# Control_Device_sch.net
KiCad netlist of a schematic drawn in Altium Designer
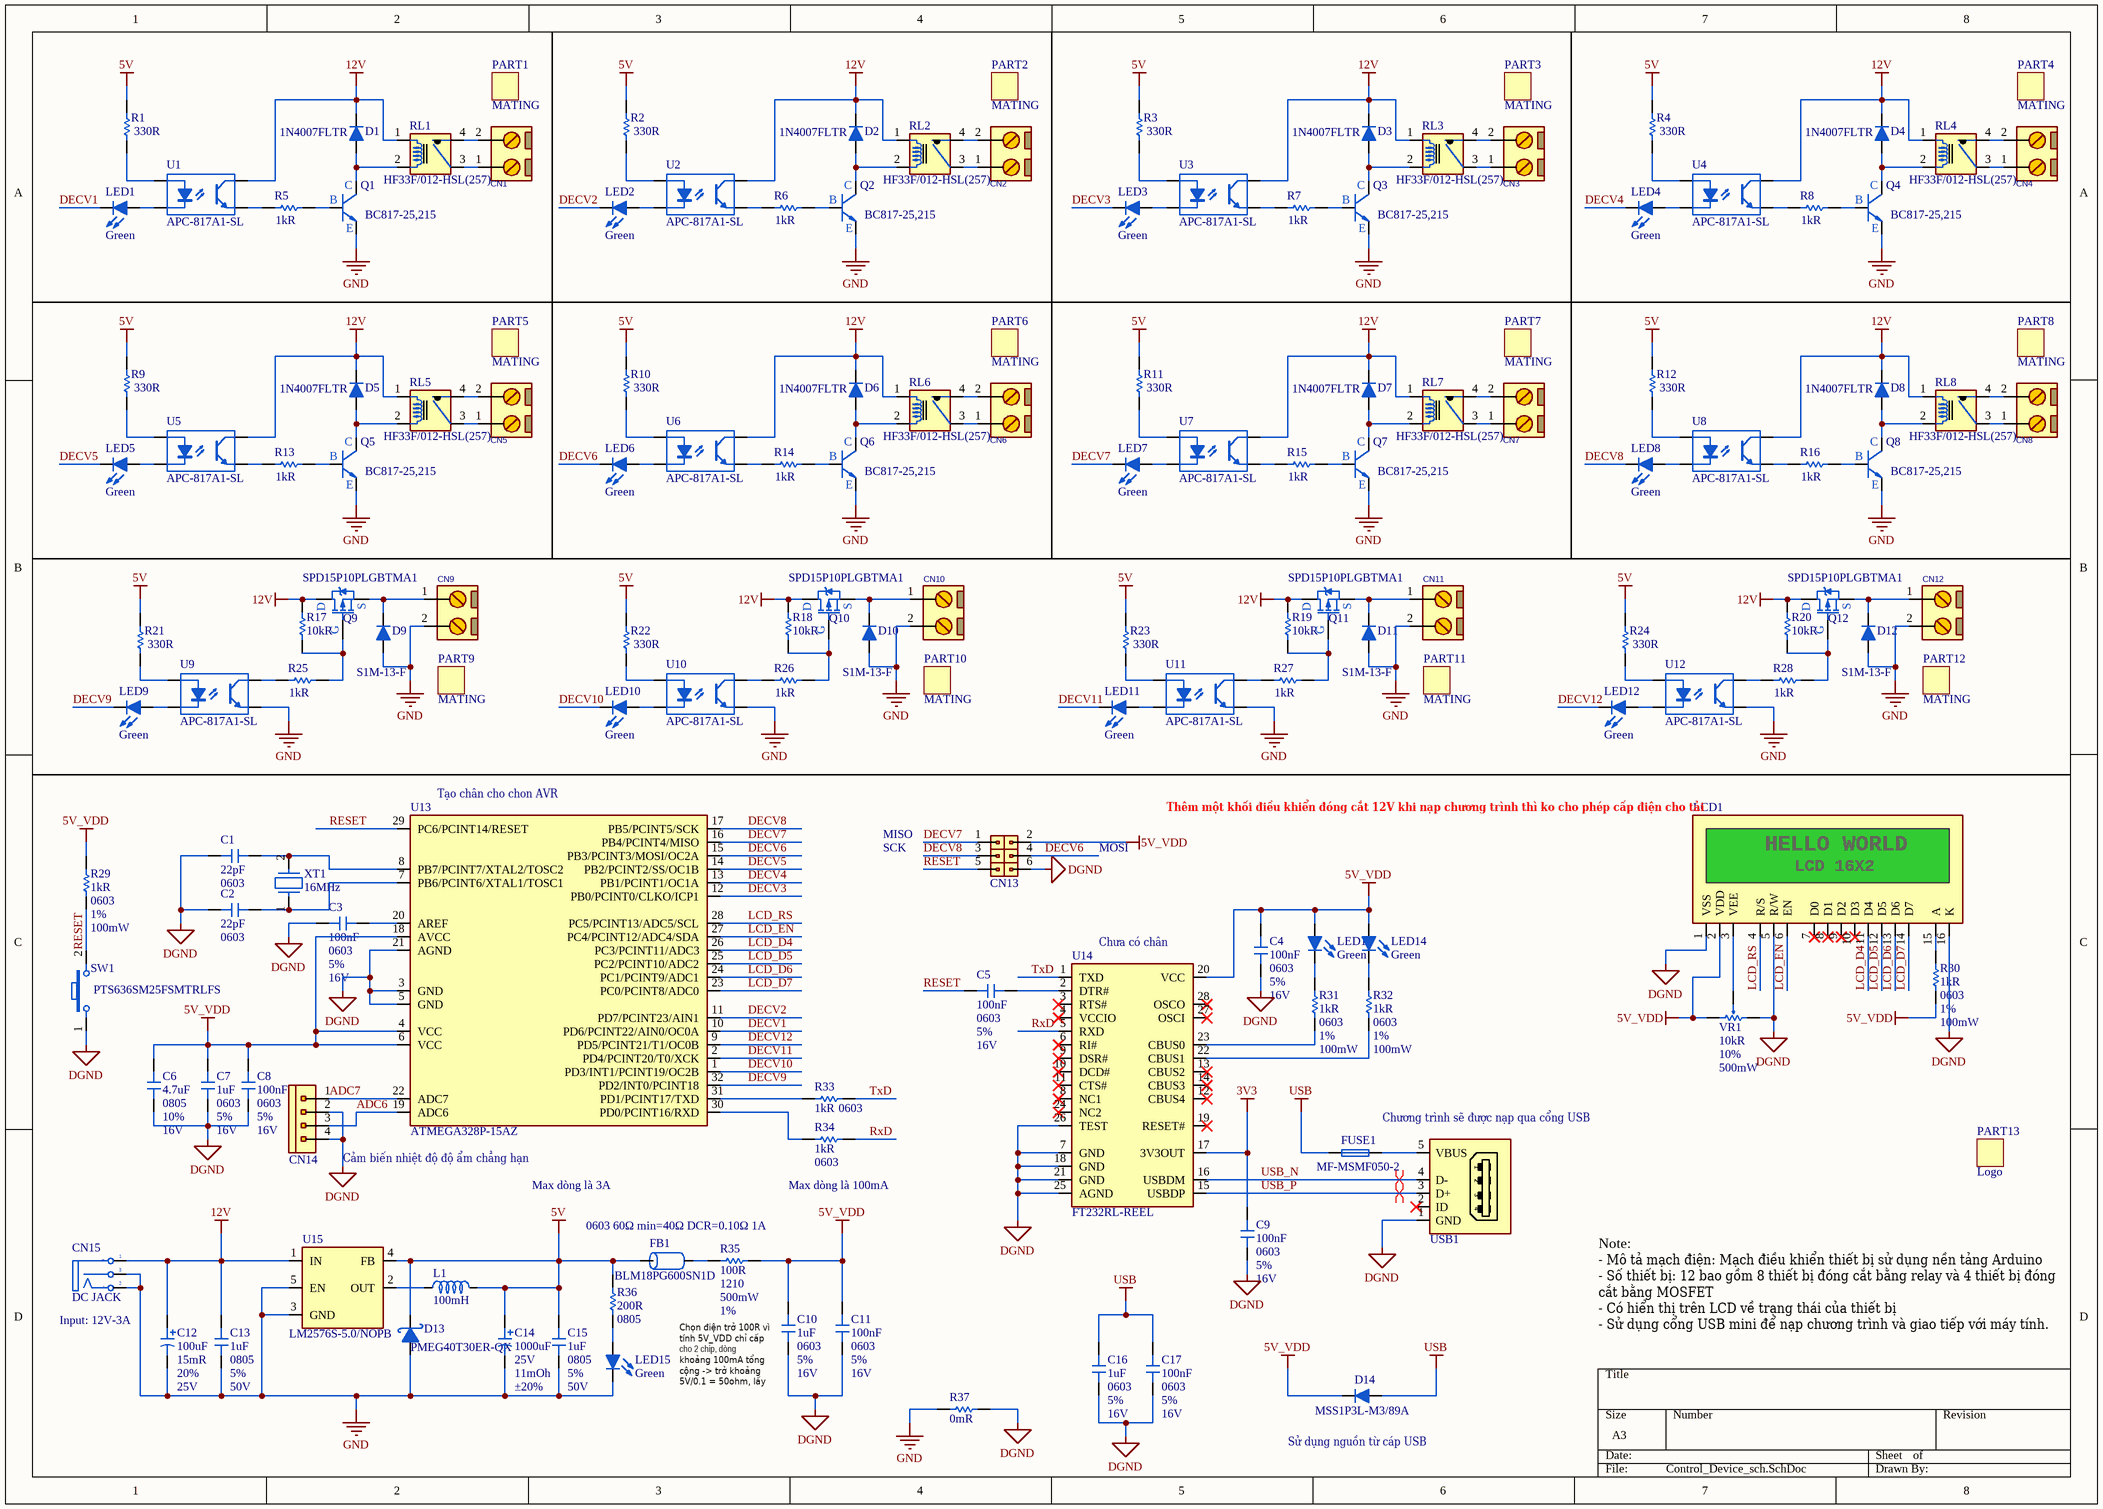
[diagram p0: Control_Device_sch.SchDoc]

(export (version "E")
  (design (tool "Eeschema 10.0.6"))
  (components
    (comp (ref "C1")
      (value "22pF")
      (footprint "C0603E")
      (description "Surface Mount Ceramic Multilayer Capacitor 22pF 5% C0G 50V 0603 Paper T/R")
      (fields
        (field (name "MANUFACTURER") "Yageo")
        (field (name "MANUFACTURER PART NUMBER") "CC0603JRNPO9BN220")
        (field (name "CASE/PACKAGE") "0603")
        (field (name "CREATOR") "hoangpt")
      )
      (libsource (lib "hoangpt") (part "CAP-CER"))
    )
    (comp (ref "C2")
      (value "22pF")
      (footprint "C0603E")
      (description "Surface Mount Ceramic Multilayer Capacitor 22pF 5% C0G 50V 0603 Paper T/R")
      (fields
        (field (name "MANUFACTURER") "Yageo")
        (field (name "MANUFACTURER PART NUMBER") "CC0603JRNPO9BN220")
        (field (name "CASE/PACKAGE") "0603")
        (field (name "CREATOR") "hoangpt")
      )
      (libsource (lib "hoangpt") (part "CAP-CER"))
    )
    (comp (ref "C3")
      (value "100nF")
      (footprint "C0603E")
      (description "Cap Ceramic 0.1uF 16V X7R 5% SMD 0603 125C T/R")
      (fields
        (field (name "MANUFACTURER") "Yageo")
        (field (name "MANUFACTURER PART NUMBER") "CC0603JRX7R7BB104")
        (field (name "CASE/PACKAGE") "0603")
        (field (name "TOLERANCE") "5%")
        (field (name "VOLTAGE RATING") "16V")
        (field (name "CREATOR") "hoangpt")
      )
      (libsource (lib "hoangpt") (part "CAP-CER"))
    )
    (comp (ref "C4")
      (value "100nF")
      (footprint "C0603E")
      (description "Cap Ceramic 0.1uF 16V X7R 5% SMD 0603 125C T/R")
      (fields
        (field (name "MANUFACTURER") "Yageo")
        (field (name "MANUFACTURER PART NUMBER") "CC0603JRX7R7BB104")
        (field (name "CASE/PACKAGE") "0603")
        (field (name "TOLERANCE") "5%")
        (field (name "VOLTAGE RATING") "16V")
        (field (name "CREATOR") "hoangpt")
      )
      (libsource (lib "hoangpt") (part "CAP-CER"))
    )
    (comp (ref "C5")
      (value "100nF")
      (footprint "C0603E")
      (description "Cap Ceramic 0.1uF 16V X7R 5% SMD 0603 125C T/R")
      (fields
        (field (name "MANUFACTURER") "Yageo")
        (field (name "MANUFACTURER PART NUMBER") "CC0603JRX7R7BB104")
        (field (name "CASE/PACKAGE") "0603")
        (field (name "TOLERANCE") "5%")
        (field (name "VOLTAGE RATING") "16V")
        (field (name "CREATOR") "hoangpt")
      )
      (libsource (lib "hoangpt") (part "CAP-CER"))
    )
    (comp (ref "C6")
      (value "4.7uF")
      (footprint "C0603E")
      (description "0805 4.7 uF 16 V ±10% Tolerance X5R Multilayer Ceramic Capacitor")
      (fields
        (field (name "MANUFACTURER") "Yageo")
        (field (name "MANUFACTURER PART NUMBER") "CC0805KKX5R7BB475")
        (field (name "CASE/PACKAGE") "0805")
        (field (name "TOLERANCE") "10%")
        (field (name "VOLTAGE RATING") "16V")
        (field (name "CREATOR") "hoangpt")
      )
      (libsource (lib "hoangpt") (part "CAP-CER"))
    )
    (comp (ref "C7")
      (value "1uF")
      (footprint "C0603E")
      (description "Cap Ceramic 1uF 16V X7R 5% SMD 0603 125°C Paper T/R")
      (fields
        (field (name "MANUFACTURER") "Yageo")
        (field (name "MANUFACTURER PART NUMBER") "CC0603JRX7R7BB105")
        (field (name "CASE/PACKAGE") "0603")
        (field (name "TOLERANCE") "5%")
        (field (name "VOLTAGE RATING") "16V")
        (field (name "CREATOR") "hoangpt")
      )
      (libsource (lib "hoangpt") (part "CAP-CER"))
    )
    (comp (ref "C8")
      (value "100nF")
      (footprint "C0603E")
      (description "Cap Ceramic 0.1uF 16V X7R 5% SMD 0603 125C T/R")
      (fields
        (field (name "MANUFACTURER") "Yageo")
        (field (name "MANUFACTURER PART NUMBER") "CC0603JRX7R7BB104")
        (field (name "CASE/PACKAGE") "0603")
        (field (name "TOLERANCE") "5%")
        (field (name "VOLTAGE RATING") "16V")
        (field (name "CREATOR") "hoangpt")
      )
      (libsource (lib "hoangpt") (part "CAP-CER"))
    )
    (comp (ref "C9")
      (value "100nF")
      (footprint "C0603E")
      (description "Cap Ceramic 0.1uF 16V X7R 5% SMD 0603 125C T/R")
      (fields
        (field (name "MANUFACTURER") "Yageo")
        (field (name "MANUFACTURER PART NUMBER") "CC0603JRX7R7BB104")
        (field (name "CASE/PACKAGE") "0603")
        (field (name "TOLERANCE") "5%")
        (field (name "VOLTAGE RATING") "16V")
        (field (name "CREATOR") "hoangpt")
      )
      (libsource (lib "hoangpt") (part "CAP-CER"))
    )
    (comp (ref "C10")
      (value "1uF")
      (footprint "C0603E")
      (description "Cap Ceramic 1uF 16V X7R 5% SMD 0603 125°C Paper T/R")
      (fields
        (field (name "MANUFACTURER") "Yageo")
        (field (name "MANUFACTURER PART NUMBER") "CC0603JRX7R7BB105")
        (field (name "CASE/PACKAGE") "0603")
        (field (name "TOLERANCE") "5%")
        (field (name "VOLTAGE RATING") "16V")
        (field (name "CREATOR") "hoangpt")
      )
      (libsource (lib "hoangpt") (part "CAP-CER"))
    )
    (comp (ref "C11")
      (value "100nF")
      (footprint "C0603E")
      (description "Cap Ceramic 0.1uF 16V X7R 5% SMD 0603 125C T/R")
      (fields
        (field (name "MANUFACTURER") "Yageo")
        (field (name "MANUFACTURER PART NUMBER") "CC0603JRX7R7BB104")
        (field (name "CASE/PACKAGE") "0603")
        (field (name "TOLERANCE") "5%")
        (field (name "VOLTAGE RATING") "16V")
        (field (name "CREATOR") "hoangpt")
      )
      (libsource (lib "hoangpt") (part "CAP-CER"))
    )
    (comp (ref "C12")
      (value "100uF")
      (footprint "CAP_ELEC_500_12X25_THD")
      (description "Cap Aluminum Polymer 100uF 25VDC 20% (10 X 12.5mm) Radial 5mm 0.015 Ohm 4500mA 2000h 105C T/R")
      (fields
        (field (name "MANUFACTURER") "Nichicon")
        (field (name "MANUFACTURER PART NUMBER") "RNS1E101MDN1PH")
        (field (name "ESR (EQUIVALENT SERIES RESISTANCE)") "15mR")
        (field (name "TOLERANCE") "20%")
        (field (name "VOLTAGE RATING") "25V")
        (field (name "CREATOR") "hoangpt")
      )
      (libsource (lib "hoangpt") (part "CAP-ELEC"))
    )
    (comp (ref "C13")
      (value "1uF")
      (footprint "C0805E")
      (description "0805 1 uF 50 V ±5 % Tolerance X7R Surface Mount Multilayer Ceramic Capacitor")
      (fields
        (field (name "MANUFACTURER") "Yageo")
        (field (name "MANUFACTURER PART NUMBER") "CC0805JKX7R9BB105")
        (field (name "CASE/PACKAGE") "0805")
        (field (name "TOLERANCE") "5%")
        (field (name "VOLTAGE RATING") "50V")
        (field (name "CREATOR") "hoangpt")
      )
      (libsource (lib "hoangpt") (part "CAP-CER"))
    )
    (comp (ref "C14")
      (value "1000uF")
      (footprint "CAP_ELEC_500_10X16_THD")
      (description "Cap, 1000Uf, 25V, Alu Elec, Hybrid, Rad Rohs Compliant: Yes")
      (fields
        (field (name "MANUFACTURER") "Panasonic")
        (field (name "MANUFACTURER PART NUMBER") "EEHAZSE102UB")
        (field (name "VOLTAGE") "25V")
        (field (name "ERS") "11mOh")
        (field (name "TOLERANCE") "±20%")
        (field (name "CREATOR") "hoangpt")
      )
      (libsource (lib "hoangpt") (part "CAP-ELEC"))
    )
    (comp (ref "C15")
      (value "1uF")
      (footprint "C0805E")
      (description "0805 1 uF 50 V ±5 % Tolerance X7R Surface Mount Multilayer Ceramic Capacitor")
      (fields
        (field (name "MANUFACTURER") "Yageo")
        (field (name "MANUFACTURER PART NUMBER") "CC0805JKX7R9BB105")
        (field (name "CASE/PACKAGE") "0805")
        (field (name "TOLERANCE") "5%")
        (field (name "VOLTAGE RATING") "50V")
        (field (name "CREATOR") "hoangpt")
      )
      (libsource (lib "hoangpt") (part "CAP-CER"))
    )
    (comp (ref "C16")
      (value "1uF")
      (footprint "C0603E")
      (description "Cap Ceramic 1uF 16V X7R 5% SMD 0603 125°C Paper T/R")
      (fields
        (field (name "MANUFACTURER") "Yageo")
        (field (name "MANUFACTURER PART NUMBER") "CC0603JRX7R7BB105")
        (field (name "CASE/PACKAGE") "0603")
        (field (name "TOLERANCE") "5%")
        (field (name "VOLTAGE RATING") "16V")
        (field (name "CREATOR") "hoangpt")
      )
      (libsource (lib "hoangpt") (part "CAP-CER"))
    )
    (comp (ref "C17")
      (value "100nF")
      (footprint "C0603E")
      (description "Cap Ceramic 0.1uF 16V X7R 5% SMD 0603 125C T/R")
      (fields
        (field (name "MANUFACTURER") "Yageo")
        (field (name "MANUFACTURER PART NUMBER") "CC0603JRX7R7BB104")
        (field (name "CASE/PACKAGE") "0603")
        (field (name "TOLERANCE") "5%")
        (field (name "VOLTAGE RATING") "16V")
        (field (name "CREATOR") "hoangpt")
      )
      (libsource (lib "hoangpt") (part "CAP-CER"))
    )
    (comp (ref "CN1")
      (value "~")
      (footprint "CON_PWR_508_H_2P")
      (description "Conn Shrouded Header (2 Sides) M 2 POS 5mm Solder RA Side Entry Thru-Hole Box")
      (fields
        (field (name "MANUFACTURER") "TE Connectivity")
        (field (name "MANUFACTURER PART NUMBER") "282812-2")
        (field (name "CREATOR") "hoangpt")
      )
      (libsource (lib "hoangpt") (part "CONN_PWR_2P"))
    )
    (comp (ref "CN2")
      (value "~")
      (footprint "CON_PWR_508_H_2P")
      (description "Conn Shrouded Header (2 Sides) M 2 POS 5mm Solder RA Side Entry Thru-Hole Box")
      (fields
        (field (name "MANUFACTURER") "TE Connectivity")
        (field (name "MANUFACTURER PART NUMBER") "282812-2")
        (field (name "CREATOR") "hoangpt")
      )
      (libsource (lib "hoangpt") (part "CONN_PWR_2P"))
    )
    (comp (ref "CN3")
      (value "~")
      (footprint "CON_PWR_508_H_2P")
      (description "Conn Shrouded Header (2 Sides) M 2 POS 5mm Solder RA Side Entry Thru-Hole Box")
      (fields
        (field (name "MANUFACTURER") "TE Connectivity")
        (field (name "MANUFACTURER PART NUMBER") "282812-2")
        (field (name "CREATOR") "hoangpt")
      )
      (libsource (lib "hoangpt") (part "CONN_PWR_2P"))
    )
    (comp (ref "CN4")
      (value "~")
      (footprint "CON_PWR_508_H_2P")
      (description "Conn Shrouded Header (2 Sides) M 2 POS 5mm Solder RA Side Entry Thru-Hole Box")
      (fields
        (field (name "MANUFACTURER") "TE Connectivity")
        (field (name "MANUFACTURER PART NUMBER") "282812-2")
        (field (name "CREATOR") "hoangpt")
      )
      (libsource (lib "hoangpt") (part "CONN_PWR_2P"))
    )
    (comp (ref "CN5")
      (value "~")
      (footprint "CON_PWR_508_H_2P")
      (description "Conn Shrouded Header (2 Sides) M 2 POS 5mm Solder RA Side Entry Thru-Hole Box")
      (fields
        (field (name "MANUFACTURER") "TE Connectivity")
        (field (name "MANUFACTURER PART NUMBER") "282812-2")
        (field (name "CREATOR") "hoangpt")
      )
      (libsource (lib "hoangpt") (part "CONN_PWR_2P"))
    )
    (comp (ref "CN6")
      (value "~")
      (footprint "CON_PWR_508_H_2P")
      (description "Conn Shrouded Header (2 Sides) M 2 POS 5mm Solder RA Side Entry Thru-Hole Box")
      (fields
        (field (name "MANUFACTURER") "TE Connectivity")
        (field (name "MANUFACTURER PART NUMBER") "282812-2")
        (field (name "CREATOR") "hoangpt")
      )
      (libsource (lib "hoangpt") (part "CONN_PWR_2P"))
    )
    (comp (ref "CN7")
      (value "~")
      (footprint "CON_PWR_508_H_2P")
      (description "Conn Shrouded Header (2 Sides) M 2 POS 5mm Solder RA Side Entry Thru-Hole Box")
      (fields
        (field (name "MANUFACTURER") "TE Connectivity")
        (field (name "MANUFACTURER PART NUMBER") "282812-2")
        (field (name "CREATOR") "hoangpt")
      )
      (libsource (lib "hoangpt") (part "CONN_PWR_2P"))
    )
    (comp (ref "CN8")
      (value "~")
      (footprint "CON_PWR_508_H_2P")
      (description "Conn Shrouded Header (2 Sides) M 2 POS 5mm Solder RA Side Entry Thru-Hole Box")
      (fields
        (field (name "MANUFACTURER") "TE Connectivity")
        (field (name "MANUFACTURER PART NUMBER") "282812-2")
        (field (name "CREATOR") "hoangpt")
      )
      (libsource (lib "hoangpt") (part "CONN_PWR_2P"))
    )
    (comp (ref "CN9")
      (value "~")
      (footprint "CON_PWR_508_H_2P")
      (description "Conn Shrouded Header (2 Sides) M 2 POS 5mm Solder RA Side Entry Thru-Hole Box")
      (fields
        (field (name "MANUFACTURER") "TE Connectivity")
        (field (name "MANUFACTURER PART NUMBER") "282812-2")
        (field (name "CREATOR") "hoangpt")
      )
      (libsource (lib "") (part "CONN_PWR_2P_1"))
    )
    (comp (ref "CN10")
      (value "~")
      (footprint "CON_PWR_508_H_2P")
      (description "Conn Shrouded Header (2 Sides) M 2 POS 5mm Solder RA Side Entry Thru-Hole Box")
      (fields
        (field (name "MANUFACTURER") "TE Connectivity")
        (field (name "MANUFACTURER PART NUMBER") "282812-2")
        (field (name "CREATOR") "hoangpt")
      )
      (libsource (lib "") (part "CONN_PWR_2P_1"))
    )
    (comp (ref "CN11")
      (value "~")
      (footprint "CON_PWR_508_H_2P")
      (description "Conn Shrouded Header (2 Sides) M 2 POS 5mm Solder RA Side Entry Thru-Hole Box")
      (fields
        (field (name "MANUFACTURER") "TE Connectivity")
        (field (name "MANUFACTURER PART NUMBER") "282812-2")
        (field (name "CREATOR") "hoangpt")
      )
      (libsource (lib "") (part "CONN_PWR_2P_1"))
    )
    (comp (ref "CN12")
      (value "~")
      (footprint "CON_PWR_508_H_2P")
      (description "Conn Shrouded Header (2 Sides) M 2 POS 5mm Solder RA Side Entry Thru-Hole Box")
      (fields
        (field (name "MANUFACTURER") "TE Connectivity")
        (field (name "MANUFACTURER PART NUMBER") "282812-2")
        (field (name "CREATOR") "hoangpt")
      )
      (libsource (lib "") (part "CONN_PWR_2P_1"))
    )
    (comp (ref "CN13")
      (value "PEC03DAAN")
      (footprint "CON_JPR_254_M_2X3")
      (description "CONN HEADER VERT 6POS 2.54MM")
      (fields (field (name "MANUFACTURER") "Sullins") (field (name "CREATOR") "hoangpt"))
      (libsource (lib "hoangpt") (part "CONN_FM_2X3P"))
    )
    (comp (ref "CN14")
      (value "~")
      (footprint "CON_JPR_254_M_1X4")
      (description "PEC Series Single Row 4 Position 2.54 mm Straight Breakaway Header")
      (fields
        (field (name "MANUFACTURER") "Sullins")
        (field (name "MANUFACTURER PART NUMBER") "PEC04SAAN")
        (field (name "CREATOR") "hoangpt")
      )
      (libsource (lib "hoangpt") (part "CONN_JP_4P"))
    )
    (comp (ref "CN15")
      (value "DC JACK")
      (footprint "JAC_DC_2MM_THD")
      (description "2.0 x 6.5 mm, 2.5 A, Horizontal, Through Hole, Dc Power Jack Connector")
      (fields (field (name "MANUFACTURER") "CUI") (field (name "MANUFACTURER PART NUMBER") "PJ-002A"))
      (libsource (lib "hoangpt") (part "DC_JACK"))
    )
    (comp (ref "D1")
      (value "1N4007FLTR")
      (footprint "D1206_SOD123_DO213AA")
      (description "Standard Rectifier 1000V SOD-123")
      (fields (field (name "MANUFACTURER") "SMC") (field (name "CREATOR") "hoangpt"))
      (libsource (lib "hoangpt") (part "DIODE"))
    )
    (comp (ref "D2")
      (value "1N4007FLTR")
      (footprint "D1206_SOD123_DO213AA")
      (description "Standard Rectifier 1000V SOD-123")
      (fields (field (name "MANUFACTURER") "SMC") (field (name "CREATOR") "hoangpt"))
      (libsource (lib "hoangpt") (part "DIODE"))
    )
    (comp (ref "D3")
      (value "1N4007FLTR")
      (footprint "D1206_SOD123_DO213AA")
      (description "Standard Rectifier 1000V SOD-123")
      (fields (field (name "MANUFACTURER") "SMC") (field (name "CREATOR") "hoangpt"))
      (libsource (lib "hoangpt") (part "DIODE"))
    )
    (comp (ref "D4")
      (value "1N4007FLTR")
      (footprint "D1206_SOD123_DO213AA")
      (description "Standard Rectifier 1000V SOD-123")
      (fields (field (name "MANUFACTURER") "SMC") (field (name "CREATOR") "hoangpt"))
      (libsource (lib "hoangpt") (part "DIODE"))
    )
    (comp (ref "D5")
      (value "1N4007FLTR")
      (footprint "D1206_SOD123_DO213AA")
      (description "Standard Rectifier 1000V SOD-123")
      (fields (field (name "MANUFACTURER") "SMC") (field (name "CREATOR") "hoangpt"))
      (libsource (lib "hoangpt") (part "DIODE"))
    )
    (comp (ref "D6")
      (value "1N4007FLTR")
      (footprint "D1206_SOD123_DO213AA")
      (description "Standard Rectifier 1000V SOD-123")
      (fields (field (name "MANUFACTURER") "SMC") (field (name "CREATOR") "hoangpt"))
      (libsource (lib "hoangpt") (part "DIODE"))
    )
    (comp (ref "D7")
      (value "1N4007FLTR")
      (footprint "D1206_SOD123_DO213AA")
      (description "Standard Rectifier 1000V SOD-123")
      (fields (field (name "MANUFACTURER") "SMC") (field (name "CREATOR") "hoangpt"))
      (libsource (lib "hoangpt") (part "DIODE"))
    )
    (comp (ref "D8")
      (value "1N4007FLTR")
      (footprint "D1206_SOD123_DO213AA")
      (description "Standard Rectifier 1000V SOD-123")
      (fields (field (name "MANUFACTURER") "SMC") (field (name "CREATOR") "hoangpt"))
      (libsource (lib "hoangpt") (part "DIODE"))
    )
    (comp (ref "D9")
      (value "S1M-13-F")
      (footprint "DIODE_SMA")
      (description "VR=1000V IF=1A 10pF Trr=3us")
      (fields (field (name "MANUFACTURER") "Diodes") (field (name "CREATOR") "hoangpt"))
      (libsource (lib "hoangpt") (part "DIODE"))
    )
    (comp (ref "D10")
      (value "S1M-13-F")
      (footprint "DIODE_SMA")
      (description "VR=1000V IF=1A 10pF Trr=3us")
      (fields (field (name "MANUFACTURER") "Diodes") (field (name "CREATOR") "hoangpt"))
      (libsource (lib "hoangpt") (part "DIODE"))
    )
    (comp (ref "D11")
      (value "S1M-13-F")
      (footprint "DIODE_SMA")
      (description "VR=1000V IF=1A 10pF Trr=3us")
      (fields (field (name "MANUFACTURER") "Diodes") (field (name "CREATOR") "hoangpt"))
      (libsource (lib "hoangpt") (part "DIODE"))
    )
    (comp (ref "D12")
      (value "S1M-13-F")
      (footprint "DIODE_SMA")
      (description "VR=1000V IF=1A 10pF Trr=3us")
      (fields (field (name "MANUFACTURER") "Diodes") (field (name "CREATOR") "hoangpt"))
      (libsource (lib "hoangpt") (part "DIODE"))
    )
    (comp (ref "D13")
      (value "PMEG40T30ER-QX")
      (footprint "DIODE_SOD123W")
      (description "PMEG40T30ER-Q - 40 V, 3 A low Trench MEGA Schottky barrier rectifier")
      (fields (field (name "MANUFACTURER") "Nexperia") (field (name "CREATOR") "hoangpt"))
      (libsource (lib "hoangpt") (part "DIODE_SCHOTTKY"))
    )
    (comp (ref "D14")
      (value "MSS1P3L-M3/89A")
      (footprint "DIODE_S457")
      (description "VR=30V IF=1A 65pF")
      (fields (field (name "MANUFACTURER") "Vishay Semiconductors") (field (name "CREATOR") "hoangpt"))
      (libsource (lib "hoangpt") (part "DIODE"))
    )
    (comp (ref "FB1")
      (value "BLM18PG600SN1D")
      (footprint "IND_L0603E_1608")
      (description "0603 60Ω min=40Ω DCR=0.10Ω 1A")
      (fields
        (field (name "MANUFACTURER") "Murata")
        (field (name "TOLERANCE") "25%")
        (field (name "CREATOR") "hoangpt")
      )
      (libsource (lib "hoangpt") (part "FERRITE BEAD"))
    )
    (comp (ref "FUSE1")
      (value "MF-MSMF050-2")
      (footprint "RFUSE")
      (description "15VDC 500mA")
      (fields (field (name "MANUFACTURER") "Bourns") (field (name "CREATOR") "hoangpt"))
      (libsource (lib "hoangpt") (part "FUSE_RESETTABLE"))
    )
    (comp (ref "L1")
      (value "100mH")
      (footprint "L_12X12")
      (description "INDUCTOR_AIR")
      (fields
        (field (name "MANUFACTURER") "Bourns")
        (field (name "MANUFACTURER PART NUMBER") "SRN3015C-101M")
        (field (name "CREATOR") "hoangpt")
      )
      (libsource (lib "hoangpt") (part "INDUCTOR_AIR"))
    )
    (comp (ref "LCD1")
      (value "~")
      (footprint "LCD_16x2")
      (description "16 x 2 Transflective White LED Backlight LCD Character Module with Heater")
      (fields
        (field (name "MANUFACTURER") "Lumex")
        (field (name "MANUFACTURER PART NUMBER") "LCR-U01602DSF/AWH")
        (field (name "CREATOR") "hoangpt")
      )
      (libsource (lib "hoangpt") (part "LCD_16X2"))
    )
    (comp (ref "LED1")
      (value "Green")
      (footprint "LED0603")
      (description "LED, Green, SMD 0805, 7.0 mcd, Green Diffused Lens")
      (fields
        (field (name "MANUFACTURER") "VCC CHML")
        (field (name "MANUFACTURER PART NUMBER") "CMD17-21VGD/TR8")
        (field (name "CREATOR") "hoangpt")
      )
      (libsource (lib "hoangpt") (part "LED"))
    )
    (comp (ref "LED2")
      (value "Green")
      (footprint "LED0603")
      (description "LED, Green, SMD 0805, 7.0 mcd, Green Diffused Lens")
      (fields
        (field (name "MANUFACTURER") "VCC CHML")
        (field (name "MANUFACTURER PART NUMBER") "CMD17-21VGD/TR8")
        (field (name "CREATOR") "hoangpt")
      )
      (libsource (lib "hoangpt") (part "LED"))
    )
    (comp (ref "LED3")
      (value "Green")
      (footprint "LED0603")
      (description "LED, Green, SMD 0805, 7.0 mcd, Green Diffused Lens")
      (fields
        (field (name "MANUFACTURER") "VCC CHML")
        (field (name "MANUFACTURER PART NUMBER") "CMD17-21VGD/TR8")
        (field (name "CREATOR") "hoangpt")
      )
      (libsource (lib "hoangpt") (part "LED"))
    )
    (comp (ref "LED4")
      (value "Green")
      (footprint "LED0603")
      (description "LED, Green, SMD 0805, 7.0 mcd, Green Diffused Lens")
      (fields
        (field (name "MANUFACTURER") "VCC CHML")
        (field (name "MANUFACTURER PART NUMBER") "CMD17-21VGD/TR8")
        (field (name "CREATOR") "hoangpt")
      )
      (libsource (lib "hoangpt") (part "LED"))
    )
    (comp (ref "LED5")
      (value "Green")
      (footprint "LED0603")
      (description "LED, Green, SMD 0805, 7.0 mcd, Green Diffused Lens")
      (fields
        (field (name "MANUFACTURER") "VCC CHML")
        (field (name "MANUFACTURER PART NUMBER") "CMD17-21VGD/TR8")
        (field (name "CREATOR") "hoangpt")
      )
      (libsource (lib "hoangpt") (part "LED"))
    )
    (comp (ref "LED6")
      (value "Green")
      (footprint "LED0603")
      (description "LED, Green, SMD 0805, 7.0 mcd, Green Diffused Lens")
      (fields
        (field (name "MANUFACTURER") "VCC CHML")
        (field (name "MANUFACTURER PART NUMBER") "CMD17-21VGD/TR8")
        (field (name "CREATOR") "hoangpt")
      )
      (libsource (lib "hoangpt") (part "LED"))
    )
    (comp (ref "LED7")
      (value "Green")
      (footprint "LED0603")
      (description "LED, Green, SMD 0805, 7.0 mcd, Green Diffused Lens")
      (fields
        (field (name "MANUFACTURER") "VCC CHML")
        (field (name "MANUFACTURER PART NUMBER") "CMD17-21VGD/TR8")
        (field (name "CREATOR") "hoangpt")
      )
      (libsource (lib "hoangpt") (part "LED"))
    )
    (comp (ref "LED8")
      (value "Green")
      (footprint "LED0603")
      (description "LED, Green, SMD 0805, 7.0 mcd, Green Diffused Lens")
      (fields
        (field (name "MANUFACTURER") "VCC CHML")
        (field (name "MANUFACTURER PART NUMBER") "CMD17-21VGD/TR8")
        (field (name "CREATOR") "hoangpt")
      )
      (libsource (lib "hoangpt") (part "LED"))
    )
    (comp (ref "LED9")
      (value "Green")
      (footprint "LED0603")
      (description "LED, Green, SMD 0805, 7.0 mcd, Green Diffused Lens")
      (fields
        (field (name "MANUFACTURER") "VCC CHML")
        (field (name "MANUFACTURER PART NUMBER") "CMD17-21VGD/TR8")
        (field (name "CREATOR") "hoangpt")
      )
      (libsource (lib "hoangpt") (part "LED"))
    )
    (comp (ref "LED10")
      (value "Green")
      (footprint "LED0603")
      (description "LED, Green, SMD 0805, 7.0 mcd, Green Diffused Lens")
      (fields
        (field (name "MANUFACTURER") "VCC CHML")
        (field (name "MANUFACTURER PART NUMBER") "CMD17-21VGD/TR8")
        (field (name "CREATOR") "hoangpt")
      )
      (libsource (lib "hoangpt") (part "LED"))
    )
    (comp (ref "LED11")
      (value "Green")
      (footprint "LED0603")
      (description "LED, Green, SMD 0805, 7.0 mcd, Green Diffused Lens")
      (fields
        (field (name "MANUFACTURER") "VCC CHML")
        (field (name "MANUFACTURER PART NUMBER") "CMD17-21VGD/TR8")
        (field (name "CREATOR") "hoangpt")
      )
      (libsource (lib "hoangpt") (part "LED"))
    )
    (comp (ref "LED12")
      (value "Green")
      (footprint "LED0603")
      (description "LED, Green, SMD 0805, 7.0 mcd, Green Diffused Lens")
      (fields
        (field (name "MANUFACTURER") "VCC CHML")
        (field (name "MANUFACTURER PART NUMBER") "CMD17-21VGD/TR8")
        (field (name "CREATOR") "hoangpt")
      )
      (libsource (lib "hoangpt") (part "LED"))
    )
    (comp (ref "LED13")
      (value "Green")
      (footprint "LED0603")
      (description "LED, Green, SMD 0805, 7.0 mcd, Green Diffused Lens")
      (fields
        (field (name "MANUFACTURER") "VCC CHML")
        (field (name "MANUFACTURER PART NUMBER") "CMD17-21VGD/TR8")
        (field (name "CREATOR") "hoangpt")
      )
      (libsource (lib "hoangpt") (part "LED"))
    )
    (comp (ref "LED14")
      (value "Green")
      (footprint "LED0603")
      (description "LED, Green, SMD 0805, 7.0 mcd, Green Diffused Lens")
      (fields
        (field (name "MANUFACTURER") "VCC CHML")
        (field (name "MANUFACTURER PART NUMBER") "CMD17-21VGD/TR8")
        (field (name "CREATOR") "hoangpt")
      )
      (libsource (lib "hoangpt") (part "LED"))
    )
    (comp (ref "LED15")
      (value "Green")
      (footprint "LED0603")
      (description "LED, Green, SMD 0805, 7.0 mcd, Green Diffused Lens")
      (fields
        (field (name "MANUFACTURER") "VCC CHML")
        (field (name "MANUFACTURER PART NUMBER") "CMD17-21VGD/TR8")
        (field (name "CREATOR") "hoangpt")
      )
      (libsource (lib "hoangpt") (part "LED"))
    )
    (comp (ref "PART1")
      (value "MATING")
      (description "Conn Terminal Block F 2 POS 5mm Screw RA Cable Mount 15A/Contact")
      (fields
        (field (name "MANUFACTURER") "TE Connectivity")
        (field (name "MANUFACTURER PART NUMBER") "796640-2")
      )
      (libsource (lib "hoangpt") (part "PART_NO-BOM"))
    )
    (comp (ref "PART2")
      (value "MATING")
      (description "Conn Terminal Block F 2 POS 5mm Screw RA Cable Mount 15A/Contact")
      (fields
        (field (name "MANUFACTURER") "TE Connectivity")
        (field (name "MANUFACTURER PART NUMBER") "796640-2")
      )
      (libsource (lib "hoangpt") (part "PART_NO-BOM"))
    )
    (comp (ref "PART3")
      (value "MATING")
      (description "Conn Terminal Block F 2 POS 5mm Screw RA Cable Mount 15A/Contact")
      (fields
        (field (name "MANUFACTURER") "TE Connectivity")
        (field (name "MANUFACTURER PART NUMBER") "796640-2")
      )
      (libsource (lib "hoangpt") (part "PART_NO-BOM"))
    )
    (comp (ref "PART4")
      (value "MATING")
      (description "Conn Terminal Block F 2 POS 5mm Screw RA Cable Mount 15A/Contact")
      (fields
        (field (name "MANUFACTURER") "TE Connectivity")
        (field (name "MANUFACTURER PART NUMBER") "796640-2")
      )
      (libsource (lib "hoangpt") (part "PART_NO-BOM"))
    )
    (comp (ref "PART5")
      (value "MATING")
      (description "Conn Terminal Block F 2 POS 5mm Screw RA Cable Mount 15A/Contact")
      (fields
        (field (name "MANUFACTURER") "TE Connectivity")
        (field (name "MANUFACTURER PART NUMBER") "796640-2")
      )
      (libsource (lib "hoangpt") (part "PART_NO-BOM"))
    )
    (comp (ref "PART6")
      (value "MATING")
      (description "Conn Terminal Block F 2 POS 5mm Screw RA Cable Mount 15A/Contact")
      (fields
        (field (name "MANUFACTURER") "TE Connectivity")
        (field (name "MANUFACTURER PART NUMBER") "796640-2")
      )
      (libsource (lib "hoangpt") (part "PART_NO-BOM"))
    )
    (comp (ref "PART7")
      (value "MATING")
      (description "Conn Terminal Block F 2 POS 5mm Screw RA Cable Mount 15A/Contact")
      (fields
        (field (name "MANUFACTURER") "TE Connectivity")
        (field (name "MANUFACTURER PART NUMBER") "796640-2")
      )
      (libsource (lib "hoangpt") (part "PART_NO-BOM"))
    )
    (comp (ref "PART8")
      (value "MATING")
      (description "Conn Terminal Block F 2 POS 5mm Screw RA Cable Mount 15A/Contact")
      (fields
        (field (name "MANUFACTURER") "TE Connectivity")
        (field (name "MANUFACTURER PART NUMBER") "796640-2")
      )
      (libsource (lib "hoangpt") (part "PART_NO-BOM"))
    )
    (comp (ref "PART9")
      (value "MATING")
      (description "Conn Terminal Block F 2 POS 5mm Screw RA Cable Mount 15A/Contact")
      (fields
        (field (name "MANUFACTURER") "TE Connectivity")
        (field (name "MANUFACTURER PART NUMBER") "796640-2")
      )
      (libsource (lib "hoangpt") (part "PART_NO-BOM"))
    )
    (comp (ref "PART10")
      (value "MATING")
      (description "Conn Terminal Block F 2 POS 5mm Screw RA Cable Mount 15A/Contact")
      (fields
        (field (name "MANUFACTURER") "TE Connectivity")
        (field (name "MANUFACTURER PART NUMBER") "796640-2")
      )
      (libsource (lib "hoangpt") (part "PART_NO-BOM"))
    )
    (comp (ref "PART11")
      (value "MATING")
      (description "Conn Terminal Block F 2 POS 5mm Screw RA Cable Mount 15A/Contact")
      (fields
        (field (name "MANUFACTURER") "TE Connectivity")
        (field (name "MANUFACTURER PART NUMBER") "796640-2")
      )
      (libsource (lib "hoangpt") (part "PART_NO-BOM"))
    )
    (comp (ref "PART12")
      (value "MATING")
      (description "Conn Terminal Block F 2 POS 5mm Screw RA Cable Mount 15A/Contact")
      (fields
        (field (name "MANUFACTURER") "TE Connectivity")
        (field (name "MANUFACTURER PART NUMBER") "796640-2")
      )
      (libsource (lib "hoangpt") (part "PART_NO-BOM"))
    )
    (comp (ref "PART13")
      (value "Logo")
      (footprint "MyLogo_5mm - Invert")
      (description "Conn Terminal Block F 2 POS 5mm Screw RA Cable Mount 15A/Contact")
      (libsource (lib "hoangpt") (part "PART_NO-BOM"))
    )
    (comp (ref "Q1")
      (value "BC817-25,215")
      (footprint "SOT23_3")
      (description "NPN Ic=500mA Vceo=45V hfe=160~400 P=250mW")
      (fields (field (name "MANUFACTURER") "Nexperia") (field (name "CREATOR") "hoangpt"))
      (libsource (lib "hoangpt") (part "NPN"))
    )
    (comp (ref "Q2")
      (value "BC817-25,215")
      (footprint "SOT23_3")
      (description "NPN Ic=500mA Vceo=45V hfe=160~400 P=250mW")
      (fields (field (name "MANUFACTURER") "Nexperia") (field (name "CREATOR") "hoangpt"))
      (libsource (lib "hoangpt") (part "NPN"))
    )
    (comp (ref "Q3")
      (value "BC817-25,215")
      (footprint "SOT23_3")
      (description "NPN Ic=500mA Vceo=45V hfe=160~400 P=250mW")
      (fields (field (name "MANUFACTURER") "Nexperia") (field (name "CREATOR") "hoangpt"))
      (libsource (lib "hoangpt") (part "NPN"))
    )
    (comp (ref "Q4")
      (value "BC817-25,215")
      (footprint "SOT23_3")
      (description "NPN Ic=500mA Vceo=45V hfe=160~400 P=250mW")
      (fields (field (name "MANUFACTURER") "Nexperia") (field (name "CREATOR") "hoangpt"))
      (libsource (lib "hoangpt") (part "NPN"))
    )
    (comp (ref "Q5")
      (value "BC817-25,215")
      (footprint "SOT23_3")
      (description "NPN Ic=500mA Vceo=45V hfe=160~400 P=250mW")
      (fields (field (name "MANUFACTURER") "Nexperia") (field (name "CREATOR") "hoangpt"))
      (libsource (lib "hoangpt") (part "NPN"))
    )
    (comp (ref "Q6")
      (value "BC817-25,215")
      (footprint "SOT23_3")
      (description "NPN Ic=500mA Vceo=45V hfe=160~400 P=250mW")
      (fields (field (name "MANUFACTURER") "Nexperia") (field (name "CREATOR") "hoangpt"))
      (libsource (lib "hoangpt") (part "NPN"))
    )
    (comp (ref "Q7")
      (value "BC817-25,215")
      (footprint "SOT23_3")
      (description "NPN Ic=500mA Vceo=45V hfe=160~400 P=250mW")
      (fields (field (name "MANUFACTURER") "Nexperia") (field (name "CREATOR") "hoangpt"))
      (libsource (lib "hoangpt") (part "NPN"))
    )
    (comp (ref "Q8")
      (value "BC817-25,215")
      (footprint "SOT23_3")
      (description "NPN Ic=500mA Vceo=45V hfe=160~400 P=250mW")
      (fields (field (name "MANUFACTURER") "Nexperia") (field (name "CREATOR") "hoangpt"))
      (libsource (lib "hoangpt") (part "NPN"))
    )
    (comp (ref "Q9")
      (value "SPD15P10PLGBTMA1")
      (footprint "DPAK3_TO-252")
      (description "MOSFET, P-CH, 100V, 15A, TO252-3; Transistor Polarity: P Channel; Continuous Drai")
      (fields (field (name "MANUFACTURER") "Infineon") (field (name "CREATOR") "hoangpt"))
      (libsource (lib "hoangpt") (part "MOSFET-P_ESD"))
    )
    (comp (ref "Q10")
      (value "SPD15P10PLGBTMA1")
      (footprint "DPAK3_TO-252")
      (description "MOSFET, P-CH, 100V, 15A, TO252-3; Transistor Polarity: P Channel; Continuous Drai")
      (fields (field (name "MANUFACTURER") "Infineon") (field (name "CREATOR") "hoangpt"))
      (libsource (lib "hoangpt") (part "MOSFET-P_ESD"))
    )
    (comp (ref "Q11")
      (value "SPD15P10PLGBTMA1")
      (footprint "DPAK3_TO-252")
      (description "MOSFET, P-CH, 100V, 15A, TO252-3; Transistor Polarity: P Channel; Continuous Drai")
      (fields (field (name "MANUFACTURER") "Infineon") (field (name "CREATOR") "hoangpt"))
      (libsource (lib "hoangpt") (part "MOSFET-P_ESD"))
    )
    (comp (ref "Q12")
      (value "SPD15P10PLGBTMA1")
      (footprint "DPAK3_TO-252")
      (description "MOSFET, P-CH, 100V, 15A, TO252-3; Transistor Polarity: P Channel; Continuous Drai")
      (fields (field (name "MANUFACTURER") "Infineon") (field (name "CREATOR") "hoangpt"))
      (libsource (lib "hoangpt") (part "MOSFET-P_ESD"))
    )
    (comp (ref "R1")
      (value "330R")
      (footprint "R0603E")
      (description "Res General Purpose Thick Film 0603 330 Ohm 5% 1/10W ±100ppm/°C Molded SMD Paper T/R")
      (fields
        (field (name "MANUFACTURER") "Yageo")
        (field (name "MANUFACTURER PART NUMBER") "RC0603JR-07330RL")
        (field (name "CREATOR") "hoangpt")
      )
      (libsource (lib "hoangpt") (part "RESISTOR"))
    )
    (comp (ref "R2")
      (value "330R")
      (footprint "R0603E")
      (description "Res General Purpose Thick Film 0603 330 Ohm 5% 1/10W ±100ppm/°C Molded SMD Paper T/R")
      (fields
        (field (name "MANUFACTURER") "Yageo")
        (field (name "MANUFACTURER PART NUMBER") "RC0603JR-07330RL")
        (field (name "CREATOR") "hoangpt")
      )
      (libsource (lib "hoangpt") (part "RESISTOR"))
    )
    (comp (ref "R3")
      (value "330R")
      (footprint "R0603E")
      (description "Res General Purpose Thick Film 0603 330 Ohm 5% 1/10W ±100ppm/°C Molded SMD Paper T/R")
      (fields
        (field (name "MANUFACTURER") "Yageo")
        (field (name "MANUFACTURER PART NUMBER") "RC0603JR-07330RL")
        (field (name "CREATOR") "hoangpt")
      )
      (libsource (lib "hoangpt") (part "RESISTOR"))
    )
    (comp (ref "R4")
      (value "330R")
      (footprint "R0603E")
      (description "Res General Purpose Thick Film 0603 330 Ohm 5% 1/10W ±100ppm/°C Molded SMD Paper T/R")
      (fields
        (field (name "MANUFACTURER") "Yageo")
        (field (name "MANUFACTURER PART NUMBER") "RC0603JR-07330RL")
        (field (name "CREATOR") "hoangpt")
      )
      (libsource (lib "hoangpt") (part "RESISTOR"))
    )
    (comp (ref "R5")
      (value "1kR")
      (footprint "R0603E")
      (description "Res Thick Film 0603 1K Ohm 1% 1/10W ±100ppm/°C Molded SMD SMD Paper T/R")
      (fields
        (field (name "MANUFACTURER") "Yageo")
        (field (name "MANUFACTURER PART NUMBER") "RC0603FR-071KL")
        (field (name "CREATOR") "hoangpt")
      )
      (libsource (lib "hoangpt") (part "RESISTOR"))
    )
    (comp (ref "R6")
      (value "1kR")
      (footprint "R0603E")
      (description "Res Thick Film 0603 1K Ohm 1% 1/10W ±100ppm/°C Molded SMD SMD Paper T/R")
      (fields
        (field (name "MANUFACTURER") "Yageo")
        (field (name "MANUFACTURER PART NUMBER") "RC0603FR-071KL")
        (field (name "CREATOR") "hoangpt")
      )
      (libsource (lib "hoangpt") (part "RESISTOR"))
    )
    (comp (ref "R7")
      (value "1kR")
      (footprint "R0603E")
      (description "Res Thick Film 0603 1K Ohm 1% 1/10W ±100ppm/°C Molded SMD SMD Paper T/R")
      (fields
        (field (name "MANUFACTURER") "Yageo")
        (field (name "MANUFACTURER PART NUMBER") "RC0603FR-071KL")
        (field (name "CREATOR") "hoangpt")
      )
      (libsource (lib "hoangpt") (part "RESISTOR"))
    )
    (comp (ref "R8")
      (value "1kR")
      (footprint "R0603E")
      (description "Res Thick Film 0603 1K Ohm 1% 1/10W ±100ppm/°C Molded SMD SMD Paper T/R")
      (fields
        (field (name "MANUFACTURER") "Yageo")
        (field (name "MANUFACTURER PART NUMBER") "RC0603FR-071KL")
        (field (name "CREATOR") "hoangpt")
      )
      (libsource (lib "hoangpt") (part "RESISTOR"))
    )
    (comp (ref "R9")
      (value "330R")
      (footprint "R0603E")
      (description "Res General Purpose Thick Film 0603 330 Ohm 5% 1/10W ±100ppm/°C Molded SMD Paper T/R")
      (fields
        (field (name "MANUFACTURER") "Yageo")
        (field (name "MANUFACTURER PART NUMBER") "RC0603JR-07330RL")
        (field (name "CREATOR") "hoangpt")
      )
      (libsource (lib "hoangpt") (part "RESISTOR"))
    )
    (comp (ref "R10")
      (value "330R")
      (footprint "R0603E")
      (description "Res General Purpose Thick Film 0603 330 Ohm 5% 1/10W ±100ppm/°C Molded SMD Paper T/R")
      (fields
        (field (name "MANUFACTURER") "Yageo")
        (field (name "MANUFACTURER PART NUMBER") "RC0603JR-07330RL")
        (field (name "CREATOR") "hoangpt")
      )
      (libsource (lib "hoangpt") (part "RESISTOR"))
    )
    (comp (ref "R11")
      (value "330R")
      (footprint "R0603E")
      (description "Res General Purpose Thick Film 0603 330 Ohm 5% 1/10W ±100ppm/°C Molded SMD Paper T/R")
      (fields
        (field (name "MANUFACTURER") "Yageo")
        (field (name "MANUFACTURER PART NUMBER") "RC0603JR-07330RL")
        (field (name "CREATOR") "hoangpt")
      )
      (libsource (lib "hoangpt") (part "RESISTOR"))
    )
    (comp (ref "R12")
      (value "330R")
      (footprint "R0603E")
      (description "Res General Purpose Thick Film 0603 330 Ohm 5% 1/10W ±100ppm/°C Molded SMD Paper T/R")
      (fields
        (field (name "MANUFACTURER") "Yageo")
        (field (name "MANUFACTURER PART NUMBER") "RC0603JR-07330RL")
        (field (name "CREATOR") "hoangpt")
      )
      (libsource (lib "hoangpt") (part "RESISTOR"))
    )
    (comp (ref "R13")
      (value "1kR")
      (footprint "R0603E")
      (description "Res Thick Film 0603 1K Ohm 1% 1/10W ±100ppm/°C Molded SMD SMD Paper T/R")
      (fields
        (field (name "MANUFACTURER") "Yageo")
        (field (name "MANUFACTURER PART NUMBER") "RC0603FR-071KL")
        (field (name "CREATOR") "hoangpt")
      )
      (libsource (lib "hoangpt") (part "RESISTOR"))
    )
    (comp (ref "R14")
      (value "1kR")
      (footprint "R0603E")
      (description "Res Thick Film 0603 1K Ohm 1% 1/10W ±100ppm/°C Molded SMD SMD Paper T/R")
      (fields
        (field (name "MANUFACTURER") "Yageo")
        (field (name "MANUFACTURER PART NUMBER") "RC0603FR-071KL")
        (field (name "CREATOR") "hoangpt")
      )
      (libsource (lib "hoangpt") (part "RESISTOR"))
    )
    (comp (ref "R15")
      (value "1kR")
      (footprint "R0603E")
      (description "Res Thick Film 0603 1K Ohm 1% 1/10W ±100ppm/°C Molded SMD SMD Paper T/R")
      (fields
        (field (name "MANUFACTURER") "Yageo")
        (field (name "MANUFACTURER PART NUMBER") "RC0603FR-071KL")
        (field (name "CREATOR") "hoangpt")
      )
      (libsource (lib "hoangpt") (part "RESISTOR"))
    )
    (comp (ref "R16")
      (value "1kR")
      (footprint "R0603E")
      (description "Res Thick Film 0603 1K Ohm 1% 1/10W ±100ppm/°C Molded SMD SMD Paper T/R")
      (fields
        (field (name "MANUFACTURER") "Yageo")
        (field (name "MANUFACTURER PART NUMBER") "RC0603FR-071KL")
        (field (name "CREATOR") "hoangpt")
      )
      (libsource (lib "hoangpt") (part "RESISTOR"))
    )
    (comp (ref "R17")
      (value "10kR")
      (footprint "R0603E")
      (description "RES SMD 10K OHM 1% 1/10W 0603")
      (fields
        (field (name "MANUFACTURER") "Yageo")
        (field (name "MANUFACTURER PART NUMBER") "RC0603FR-0710KL")
        (field (name "CREATOR") "hoangpt")
      )
      (libsource (lib "hoangpt") (part "RESISTOR"))
    )
    (comp (ref "R18")
      (value "10kR")
      (footprint "R0603E")
      (description "RES SMD 10K OHM 1% 1/10W 0603")
      (fields
        (field (name "MANUFACTURER") "Yageo")
        (field (name "MANUFACTURER PART NUMBER") "RC0603FR-0710KL")
        (field (name "CREATOR") "hoangpt")
      )
      (libsource (lib "hoangpt") (part "RESISTOR"))
    )
    (comp (ref "R19")
      (value "10kR")
      (footprint "R0603E")
      (description "RES SMD 10K OHM 1% 1/10W 0603")
      (fields
        (field (name "MANUFACTURER") "Yageo")
        (field (name "MANUFACTURER PART NUMBER") "RC0603FR-0710KL")
        (field (name "CREATOR") "hoangpt")
      )
      (libsource (lib "hoangpt") (part "RESISTOR"))
    )
    (comp (ref "R20")
      (value "10kR")
      (footprint "R0603E")
      (description "RES SMD 10K OHM 1% 1/10W 0603")
      (fields
        (field (name "MANUFACTURER") "Yageo")
        (field (name "MANUFACTURER PART NUMBER") "RC0603FR-0710KL")
        (field (name "CREATOR") "hoangpt")
      )
      (libsource (lib "hoangpt") (part "RESISTOR"))
    )
    (comp (ref "R21")
      (value "330R")
      (footprint "R0603E")
      (description "Res General Purpose Thick Film 0603 330 Ohm 5% 1/10W ±100ppm/°C Molded SMD Paper T/R")
      (fields
        (field (name "MANUFACTURER") "Yageo")
        (field (name "MANUFACTURER PART NUMBER") "RC0603JR-07330RL")
        (field (name "CREATOR") "hoangpt")
      )
      (libsource (lib "hoangpt") (part "RESISTOR"))
    )
    (comp (ref "R22")
      (value "330R")
      (footprint "R0603E")
      (description "Res General Purpose Thick Film 0603 330 Ohm 5% 1/10W ±100ppm/°C Molded SMD Paper T/R")
      (fields
        (field (name "MANUFACTURER") "Yageo")
        (field (name "MANUFACTURER PART NUMBER") "RC0603JR-07330RL")
        (field (name "CREATOR") "hoangpt")
      )
      (libsource (lib "hoangpt") (part "RESISTOR"))
    )
    (comp (ref "R23")
      (value "330R")
      (footprint "R0603E")
      (description "Res General Purpose Thick Film 0603 330 Ohm 5% 1/10W ±100ppm/°C Molded SMD Paper T/R")
      (fields
        (field (name "MANUFACTURER") "Yageo")
        (field (name "MANUFACTURER PART NUMBER") "RC0603JR-07330RL")
        (field (name "CREATOR") "hoangpt")
      )
      (libsource (lib "hoangpt") (part "RESISTOR"))
    )
    (comp (ref "R24")
      (value "330R")
      (footprint "R0603E")
      (description "Res General Purpose Thick Film 0603 330 Ohm 5% 1/10W ±100ppm/°C Molded SMD Paper T/R")
      (fields
        (field (name "MANUFACTURER") "Yageo")
        (field (name "MANUFACTURER PART NUMBER") "RC0603JR-07330RL")
        (field (name "CREATOR") "hoangpt")
      )
      (libsource (lib "hoangpt") (part "RESISTOR"))
    )
    (comp (ref "R25")
      (value "1kR")
      (footprint "R0603E")
      (description "Res Thick Film 0603 1K Ohm 1% 1/10W ±100ppm/°C Molded SMD SMD Paper T/R")
      (fields
        (field (name "MANUFACTURER") "Yageo")
        (field (name "MANUFACTURER PART NUMBER") "RC0603FR-071KL")
        (field (name "CREATOR") "hoangpt")
      )
      (libsource (lib "hoangpt") (part "RESISTOR"))
    )
    (comp (ref "R26")
      (value "1kR")
      (footprint "R0603E")
      (description "Res Thick Film 0603 1K Ohm 1% 1/10W ±100ppm/°C Molded SMD SMD Paper T/R")
      (fields
        (field (name "MANUFACTURER") "Yageo")
        (field (name "MANUFACTURER PART NUMBER") "RC0603FR-071KL")
        (field (name "CREATOR") "hoangpt")
      )
      (libsource (lib "hoangpt") (part "RESISTOR"))
    )
    (comp (ref "R27")
      (value "1kR")
      (footprint "R0603E")
      (description "Res Thick Film 0603 1K Ohm 1% 1/10W ±100ppm/°C Molded SMD SMD Paper T/R")
      (fields
        (field (name "MANUFACTURER") "Yageo")
        (field (name "MANUFACTURER PART NUMBER") "RC0603FR-071KL")
        (field (name "CREATOR") "hoangpt")
      )
      (libsource (lib "hoangpt") (part "RESISTOR"))
    )
    (comp (ref "R28")
      (value "1kR")
      (footprint "R0603E")
      (description "Res Thick Film 0603 1K Ohm 1% 1/10W ±100ppm/°C Molded SMD SMD Paper T/R")
      (fields
        (field (name "MANUFACTURER") "Yageo")
        (field (name "MANUFACTURER PART NUMBER") "RC0603FR-071KL")
        (field (name "CREATOR") "hoangpt")
      )
      (libsource (lib "hoangpt") (part "RESISTOR"))
    )
    (comp (ref "R29")
      (value "1kR")
      (footprint "R0603E")
      (description "Res Thick Film 0603 1K Ohm 1% 1/10W ±100ppm/°C Molded SMD SMD Paper T/R")
      (fields
        (field (name "MANUFACTURER") "Yageo")
        (field (name "MANUFACTURER PART NUMBER") "RC0603FR-071KL")
        (field (name "CASE/PACKAGE") "0603")
        (field (name "TOLERANCE") "1%")
        (field (name "MAX POWER DISSIPATION") "100mW")
        (field (name "CREATOR") "hoangpt")
      )
      (libsource (lib "hoangpt") (part "RESISTOR"))
    )
    (comp (ref "R30")
      (value "1kR")
      (footprint "R0603E")
      (description "Res Thick Film 0603 1K Ohm 1% 1/10W ±100ppm/°C Molded SMD SMD Paper T/R")
      (fields
        (field (name "MANUFACTURER") "Yageo")
        (field (name "MANUFACTURER PART NUMBER") "RC0603FR-071KL")
        (field (name "CASE/PACKAGE") "0603")
        (field (name "TOLERANCE") "1%")
        (field (name "MAX POWER DISSIPATION") "100mW")
        (field (name "CREATOR") "hoangpt")
      )
      (libsource (lib "hoangpt") (part "RESISTOR"))
    )
    (comp (ref "R31")
      (value "1kR")
      (footprint "R0603E")
      (description "Res Thick Film 0603 1K Ohm 1% 1/10W ±100ppm/°C Molded SMD SMD Paper T/R")
      (fields
        (field (name "MANUFACTURER") "Yageo")
        (field (name "MANUFACTURER PART NUMBER") "RC0603FR-071KL")
        (field (name "CASE/PACKAGE") "0603")
        (field (name "TOLERANCE") "1%")
        (field (name "MAX POWER DISSIPATION") "100mW")
        (field (name "CREATOR") "hoangpt")
      )
      (libsource (lib "hoangpt") (part "RESISTOR"))
    )
    (comp (ref "R32")
      (value "1kR")
      (footprint "R0603E")
      (description "Res Thick Film 0603 1K Ohm 1% 1/10W ±100ppm/°C Molded SMD SMD Paper T/R")
      (fields
        (field (name "MANUFACTURER") "Yageo")
        (field (name "MANUFACTURER PART NUMBER") "RC0603FR-071KL")
        (field (name "CASE/PACKAGE") "0603")
        (field (name "TOLERANCE") "1%")
        (field (name "MAX POWER DISSIPATION") "100mW")
        (field (name "CREATOR") "hoangpt")
      )
      (libsource (lib "hoangpt") (part "RESISTOR"))
    )
    (comp (ref "R33")
      (value "1kR")
      (footprint "R0603E")
      (description "Res Thick Film 0603 1K Ohm 1% 1/10W ±100ppm/°C Molded SMD SMD Paper T/R")
      (fields
        (field (name "MANUFACTURER") "Yageo")
        (field (name "MANUFACTURER PART NUMBER") "RC0603FR-071KL")
        (field (name "CASE/PACKAGE") "0603")
        (field (name "CREATOR") "hoangpt")
      )
      (libsource (lib "hoangpt") (part "RESISTOR"))
    )
    (comp (ref "R34")
      (value "1kR")
      (footprint "R0603E")
      (description "Res Thick Film 0603 1K Ohm 1% 1/10W ±100ppm/°C Molded SMD SMD Paper T/R")
      (fields
        (field (name "MANUFACTURER") "Yageo")
        (field (name "MANUFACTURER PART NUMBER") "RC0603FR-071KL")
        (field (name "CASE/PACKAGE") "0603")
        (field (name "CREATOR") "hoangpt")
      )
      (libsource (lib "hoangpt") (part "RESISTOR"))
    )
    (comp (ref "R35")
      (value "100R")
      (footprint "R1210")
      (description "RES SMD 100 OHM 1% 1/2W 1210")
      (fields
        (field (name "MANUFACTURER") "Yageo")
        (field (name "MANUFACTURER PART NUMBER") "RC1210FR-07100RL")
        (field (name "CASE/PACKAGE") "1210")
        (field (name "POWER RATING") "500mW")
        (field (name "TOLERANCE") "1%")
        (field (name "CREATOR") "hoangpt")
      )
      (libsource (lib "hoangpt") (part "RESISTOR"))
    )
    (comp (ref "R36")
      (value "200R")
      (footprint "R0805E")
      (description "Res General Purpose Thick Film 0805 200 Ohm 1% 1/8W ±100ppm/°C Molded SMD Paper T/R")
      (fields
        (field (name "MANUFACTURER") "Yageo")
        (field (name "MANUFACTURER PART NUMBER") "RC0805FR-07200RL")
        (field (name "CASE/PACKAGE") "0805")
        (field (name "CREATOR") "hoangpt")
      )
      (libsource (lib "hoangpt") (part "RESISTOR"))
    )
    (comp (ref "R37")
      (value "0mR")
      (footprint "R1210")
      (description "RES SMD 0 OHM JUMPER 1/10W 0603")
      (fields
        (field (name "MANUFACTURER") "Yageo")
        (field (name "MANUFACTURER PART NUMBER") "RC0603JR-070RL")
        (field (name "CREATOR") "hoangpt")
      )
      (libsource (lib "hoangpt") (part "RESISTOR"))
    )
    (comp (ref "RL1")
      (value "HF33F/012-HSL(257)")
      (footprint "RELAY_HF33F-Form-A")
      (description "HF33F Series 10 A SPST 12 VDC PCB Mount Subminiature Intermediate Power Relay")
      (fields (field (name "MANUFACTURER") "Hongfa") (field (name "CREATOR") "hoangpt"))
      (libsource (lib "hoangpt") (part "RELAY_4P"))
    )
    (comp (ref "RL2")
      (value "HF33F/012-HSL(257)")
      (footprint "RELAY_HF33F-Form-A")
      (description "HF33F Series 10 A SPST 12 VDC PCB Mount Subminiature Intermediate Power Relay")
      (fields (field (name "MANUFACTURER") "Hongfa") (field (name "CREATOR") "hoangpt"))
      (libsource (lib "hoangpt") (part "RELAY_4P"))
    )
    (comp (ref "RL3")
      (value "HF33F/012-HSL(257)")
      (footprint "RELAY_HF33F-Form-A")
      (description "HF33F Series 10 A SPST 12 VDC PCB Mount Subminiature Intermediate Power Relay")
      (fields (field (name "MANUFACTURER") "Hongfa") (field (name "CREATOR") "hoangpt"))
      (libsource (lib "hoangpt") (part "RELAY_4P"))
    )
    (comp (ref "RL4")
      (value "HF33F/012-HSL(257)")
      (footprint "RELAY_HF33F-Form-A")
      (description "HF33F Series 10 A SPST 12 VDC PCB Mount Subminiature Intermediate Power Relay")
      (fields (field (name "MANUFACTURER") "Hongfa") (field (name "CREATOR") "hoangpt"))
      (libsource (lib "hoangpt") (part "RELAY_4P"))
    )
    (comp (ref "RL5")
      (value "HF33F/012-HSL(257)")
      (footprint "RELAY_HF33F-Form-A")
      (description "HF33F Series 10 A SPST 12 VDC PCB Mount Subminiature Intermediate Power Relay")
      (fields (field (name "MANUFACTURER") "Hongfa") (field (name "CREATOR") "hoangpt"))
      (libsource (lib "hoangpt") (part "RELAY_4P"))
    )
    (comp (ref "RL6")
      (value "HF33F/012-HSL(257)")
      (footprint "RELAY_HF33F-Form-A")
      (description "HF33F Series 10 A SPST 12 VDC PCB Mount Subminiature Intermediate Power Relay")
      (fields (field (name "MANUFACTURER") "Hongfa") (field (name "CREATOR") "hoangpt"))
      (libsource (lib "hoangpt") (part "RELAY_4P"))
    )
    (comp (ref "RL7")
      (value "HF33F/012-HSL(257)")
      (footprint "RELAY_HF33F-Form-A")
      (description "HF33F Series 10 A SPST 12 VDC PCB Mount Subminiature Intermediate Power Relay")
      (fields (field (name "MANUFACTURER") "Hongfa") (field (name "CREATOR") "hoangpt"))
      (libsource (lib "hoangpt") (part "RELAY_4P"))
    )
    (comp (ref "RL8")
      (value "HF33F/012-HSL(257)")
      (footprint "RELAY_HF33F-Form-A")
      (description "HF33F Series 10 A SPST 12 VDC PCB Mount Subminiature Intermediate Power Relay")
      (fields (field (name "MANUFACTURER") "Hongfa") (field (name "CREATOR") "hoangpt"))
      (libsource (lib "hoangpt") (part "RELAY_4P"))
    )
    (comp (ref "SW1")
      (value "PTS636SM25FSMTRLFS")
      (footprint "SW2-SMD")
      (description "PTS636 Series SPST-NO Off-Mom 180 gf Top Actuated F Lead SMT Tactile Switch")
      (fields (field (name "MANUFACTURER") "ITT C&K") (field (name "CREATOR") "hoangpt"))
      (libsource (lib "hoangpt") (part "SW2"))
    )
    (comp (ref "U1")
      (value "APC-817A1-SL")
      (footprint "SO_4")
      (description "DIP4, DC Input, Photo Transistor")
      (fields (field (name "MANUFACTURER") "American Bright") (field (name "CREATOR") "hoangpt"))
      (libsource (lib "hoangpt") (part "OPTO_TRANS"))
    )
    (comp (ref "U2")
      (value "APC-817A1-SL")
      (footprint "SO_4")
      (description "DIP4, DC Input, Photo Transistor")
      (fields (field (name "MANUFACTURER") "American Bright") (field (name "CREATOR") "hoangpt"))
      (libsource (lib "hoangpt") (part "OPTO_TRANS"))
    )
    (comp (ref "U3")
      (value "APC-817A1-SL")
      (footprint "SO_4")
      (description "DIP4, DC Input, Photo Transistor")
      (fields (field (name "MANUFACTURER") "American Bright") (field (name "CREATOR") "hoangpt"))
      (libsource (lib "hoangpt") (part "OPTO_TRANS"))
    )
    (comp (ref "U4")
      (value "APC-817A1-SL")
      (footprint "SO_4")
      (description "DIP4, DC Input, Photo Transistor")
      (fields (field (name "MANUFACTURER") "American Bright") (field (name "CREATOR") "hoangpt"))
      (libsource (lib "hoangpt") (part "OPTO_TRANS"))
    )
    (comp (ref "U5")
      (value "APC-817A1-SL")
      (footprint "SO_4")
      (description "DIP4, DC Input, Photo Transistor")
      (fields (field (name "MANUFACTURER") "American Bright") (field (name "CREATOR") "hoangpt"))
      (libsource (lib "hoangpt") (part "OPTO_TRANS"))
    )
    (comp (ref "U6")
      (value "APC-817A1-SL")
      (footprint "SO_4")
      (description "DIP4, DC Input, Photo Transistor")
      (fields (field (name "MANUFACTURER") "American Bright") (field (name "CREATOR") "hoangpt"))
      (libsource (lib "hoangpt") (part "OPTO_TRANS"))
    )
    (comp (ref "U7")
      (value "APC-817A1-SL")
      (footprint "SO_4")
      (description "DIP4, DC Input, Photo Transistor")
      (fields (field (name "MANUFACTURER") "American Bright") (field (name "CREATOR") "hoangpt"))
      (libsource (lib "hoangpt") (part "OPTO_TRANS"))
    )
    (comp (ref "U8")
      (value "APC-817A1-SL")
      (footprint "SO_4")
      (description "DIP4, DC Input, Photo Transistor")
      (fields (field (name "MANUFACTURER") "American Bright") (field (name "CREATOR") "hoangpt"))
      (libsource (lib "hoangpt") (part "OPTO_TRANS"))
    )
    (comp (ref "U9")
      (value "APC-817A1-SL")
      (footprint "SO_4")
      (description "DIP4, DC Input, Photo Transistor")
      (fields (field (name "MANUFACTURER") "American Bright") (field (name "CREATOR") "hoangpt"))
      (libsource (lib "hoangpt") (part "OPTO_TRANS"))
    )
    (comp (ref "U10")
      (value "APC-817A1-SL")
      (footprint "SO_4")
      (description "DIP4, DC Input, Photo Transistor")
      (fields (field (name "MANUFACTURER") "American Bright") (field (name "CREATOR") "hoangpt"))
      (libsource (lib "hoangpt") (part "OPTO_TRANS"))
    )
    (comp (ref "U11")
      (value "APC-817A1-SL")
      (footprint "SO_4")
      (description "DIP4, DC Input, Photo Transistor")
      (fields (field (name "MANUFACTURER") "American Bright") (field (name "CREATOR") "hoangpt"))
      (libsource (lib "hoangpt") (part "OPTO_TRANS"))
    )
    (comp (ref "U12")
      (value "APC-817A1-SL")
      (footprint "SO_4")
      (description "DIP4, DC Input, Photo Transistor")
      (fields (field (name "MANUFACTURER") "American Bright") (field (name "CREATOR") "hoangpt"))
      (libsource (lib "hoangpt") (part "OPTO_TRANS"))
    )
    (comp (ref "U13")
      (value "ATMEGA328P-15AZ")
      (footprint "TQFP80P900X900X120-32N")
      (description "8-bit AVR MCU, 32 KB, 2048 Bytes, 20 MHz, 1.8 to 5.5V, TQFP-32, RoHS")
      (fields (field (name "MANUFACTURER") "Microchip"))
      (libsource (lib "hoangpt") (part "ATMEGA328"))
    )
    (comp (ref "U14")
      (value "FT232RL-REEL")
      (footprint "SOP65P780X200-28N")
      (description "IC USB FS SERIAL UART 28-SSOP")
      (fields (field (name "MANUFACTURER") "FTDI") (field (name "VOLTAGE") "5V"))
      (libsource (lib "hoangpt") (part "FT232RL"))
    )
    (comp (ref "U15")
      (value "LM2576S-5.0/NOPB")
      (footprint "D2PAK_5P")
      (description "SIMPLE SWITCHER® 40V, 3A Low Component Count Step-Down Regulator 5-DDPAK/TO-263 -40 to 125")
      (fields (field (name "MANUFACTURER") "TI National Semiconductor") (field (name "CREATOR") "hoangpt"))
      (libsource (lib "hoangpt") (part "LM257X"))
    )
    (comp (ref "USB1")
      (value "CONN_USB_MICROB")
      (footprint "USB_MICRO_B_BM_SHT2")
      (description "CONN RCPT MICRO USB R/A SMD")
      (fields (field (name "MANF_P#") "10103593-0001LF") (field (name "MANF") "FCI"))
      (libsource (lib "hoangpt") (part "CONN_USB_MICRO_B"))
    )
    (comp (ref "VR1")
      (value "10kR")
      (footprint "POT_3362H")
      (description "Trimmer, Cermet, Rest 10 Kilohms, PCB, 1 Turns, Pwr-Rtg 0.5 W, Tol 10%")
      (fields
        (field (name "MANUFACTURER") "Bourns")
        (field (name "MANUFACTURER PART NUMBER") "3362P-1-103LF")
        (field (name "TOLERANCE") "10%")
        (field (name "POWER RATING") "500mW")
        (field (name "CREATOR") "hoangpt")
      )
      (libsource (lib "hoangpt") (part "POT-SINGLE"))
    )
    (comp (ref "XT1")
      (value "16MHz")
      (footprint "XT_2P_THD")
      (description "Crystal 16.0000MHZ 22PF Th")
      (fields
        (field (name "MANUFACTURER") "IQD")
        (field (name "MANUFACTURER PART NUMBER") "LFXTAL027945BULK")
        (field (name "CREATOR") "hoangpt")
      )
      (libsource (lib "hoangpt") (part "XTAL"))
    )
  )
  (nets
    (net (code "1") (name "/ADC6") (class "Default")
      (node (ref "CN14") (pin "3") (pinfunction "3_3") (pintype "passive"))
      (node (ref "U13") (pin "19") (pinfunction "ADC6_19") (pintype "passive"))
    )
    (net (code "2") (name "/ADC7") (class "Default")
      (node (ref "CN14") (pin "1") (pinfunction "1_1") (pintype "passive"))
      (node (ref "U13") (pin "22") (pinfunction "ADC7_22") (pintype "passive"))
    )
    (net (code "3") (name "/DECV1") (class "Default")
      (node (ref "LED1") (pin "2") (pinfunction "K_2") (pintype "passive"))
      (node (ref "U13") (pin "10") (pinfunction "PD6/PCINT22/AIN0/OC0A_10") (pintype "passive"))
    )
    (net (code "4") (name "/DECV2") (class "Default")
      (node (ref "LED2") (pin "2") (pinfunction "K_2") (pintype "passive"))
      (node (ref "U13") (pin "11") (pinfunction "PD7/PCINT23/AIN1_11") (pintype "passive"))
    )
    (net (code "5") (name "/DECV3") (class "Default")
      (node (ref "LED3") (pin "2") (pinfunction "K_2") (pintype "passive"))
      (node (ref "U13") (pin "12") (pinfunction "PB0/PCINT0/CLKO/ICP1_12") (pintype "passive"))
    )
    (net (code "6") (name "/DECV4") (class "Default")
      (node (ref "LED4") (pin "2") (pinfunction "K_2") (pintype "passive"))
      (node (ref "U13") (pin "13") (pinfunction "PB1/PCINT1/OC1A_13") (pintype "passive"))
    )
    (net (code "7") (name "/DECV5") (class "Default")
      (node (ref "LED5") (pin "2") (pinfunction "K_2") (pintype "passive"))
      (node (ref "U13") (pin "14") (pinfunction "PB2/PCINT2/SS/OC1B_14") (pintype "passive"))
    )
    (net (code "8") (name "/DECV6") (class "Default")
      (node (ref "CN13") (pin "4") (pinfunction "4_4") (pintype "passive"))
      (node (ref "LED6") (pin "2") (pinfunction "K_2") (pintype "passive"))
      (node (ref "U13") (pin "15") (pinfunction "PB3/PCINT3/MOSI/OC2A_15") (pintype "passive"))
    )
    (net (code "9") (name "/DECV7") (class "Default")
      (node (ref "CN13") (pin "1") (pinfunction "1_1") (pintype "passive"))
      (node (ref "LED7") (pin "2") (pinfunction "K_2") (pintype "passive"))
      (node (ref "U13") (pin "16") (pinfunction "PB4/PCINT4/MISO_16") (pintype "passive"))
    )
    (net (code "10") (name "/DECV8") (class "Default")
      (node (ref "CN13") (pin "3") (pinfunction "3_3") (pintype "passive"))
      (node (ref "LED8") (pin "2") (pinfunction "K_2") (pintype "passive"))
      (node (ref "U13") (pin "17") (pinfunction "PB5/PCINT5/SCK_17") (pintype "passive"))
    )
    (net (code "11") (name "/DECV9") (class "Default")
      (node (ref "LED9") (pin "2") (pinfunction "K_2") (pintype "passive"))
      (node (ref "U13") (pin "32") (pinfunction "PD2/INT0/PCINT18_32") (pintype "passive"))
    )
    (net (code "12") (name "/DECV10") (class "Default")
      (node (ref "LED10") (pin "2") (pinfunction "K_2") (pintype "passive"))
      (node (ref "U13") (pin "1") (pinfunction "PD3/INT1/PCINT19/OC2B_1") (pintype "passive"))
    )
    (net (code "13") (name "/DECV11") (class "Default")
      (node (ref "LED11") (pin "2") (pinfunction "K_2") (pintype "passive"))
      (node (ref "U13") (pin "2") (pinfunction "PD4/PCINT20/T0/XCK_2") (pintype "passive"))
    )
    (net (code "14") (name "/DECV12") (class "Default")
      (node (ref "LED12") (pin "2") (pinfunction "K_2") (pintype "passive"))
      (node (ref "U13") (pin "9") (pinfunction "PD5/PCINT21/T1/OC0B_9") (pintype "passive"))
    )
    (net (code "15") (name "/LCD_D4") (class "Default")
      (node (ref "LCD1") (pin "11") (pinfunction "D4_11") (pintype "passive"))
      (node (ref "U13") (pin "26") (pinfunction "PC3/PCINT11/ADC3_26") (pintype "passive"))
    )
    (net (code "16") (name "/LCD_D5") (class "Default")
      (node (ref "LCD1") (pin "12") (pinfunction "D5_12") (pintype "passive"))
      (node (ref "U13") (pin "25") (pinfunction "PC2/PCINT10/ADC2_25") (pintype "passive"))
    )
    (net (code "17") (name "/LCD_D6") (class "Default")
      (node (ref "LCD1") (pin "13") (pinfunction "D6_13") (pintype "passive"))
      (node (ref "U13") (pin "24") (pinfunction "PC1/PCINT9/ADC1_24") (pintype "passive"))
    )
    (net (code "18") (name "/LCD_D7") (class "Default")
      (node (ref "LCD1") (pin "14") (pinfunction "D7_14") (pintype "passive"))
      (node (ref "U13") (pin "23") (pinfunction "PC0/PCINT8/ADC0_23") (pintype "passive"))
    )
    (net (code "19") (name "/LCD_EN") (class "Default")
      (node (ref "LCD1") (pin "6") (pinfunction "EN_6") (pintype "passive"))
      (node (ref "U13") (pin "27") (pinfunction "PC4/PCINT12/ADC4/SDA_27") (pintype "passive"))
    )
    (net (code "20") (name "/LCD_RS") (class "Default")
      (node (ref "LCD1") (pin "4") (pinfunction "R/S_4") (pintype "passive"))
      (node (ref "U13") (pin "28") (pinfunction "PC5/PCINT13/ADC5/SCL_28") (pintype "passive"))
    )
    (net (code "21") (name "/RESET") (class "Default")
      (node (ref "C5") (pin "2") (pinfunction "2_2") (pintype "passive"))
      (node (ref "CN13") (pin "5") (pinfunction "5_5") (pintype "passive"))
      (node (ref "R29") (pin "1") (pinfunction "1_1") (pintype "passive"))
      (node (ref "SW1") (pin "2") (pintype "passive"))
      (node (ref "U13") (pin "29") (pinfunction "PC6/PCINT14/RESET_29") (pintype "passive"))
    )
    (net (code "22") (name "/RxD") (class "Default")
      (node (ref "R34") (pin "1") (pinfunction "1_1") (pintype "passive"))
      (node (ref "U14") (pin "5") (pinfunction "RXD_5") (pintype "passive"))
    )
    (net (code "23") (name "/TxD") (class "Default")
      (node (ref "R33") (pin "1") (pinfunction "1_1") (pintype "passive"))
      (node (ref "U14") (pin "1") (pinfunction "TXD_1") (pintype "passive"))
    )
    (net (code "24") (name "/USB_N") (class "Default")
      (node (ref "U14") (pin "16") (pinfunction "USBDM_16") (pintype "passive"))
      (node (ref "USB1") (pin "4") (pinfunction "D-_4") (pintype "passive"))
    )
    (net (code "25") (name "/USB_P") (class "Default")
      (node (ref "U14") (pin "15") (pinfunction "USBDP_15") (pintype "passive"))
      (node (ref "USB1") (pin "3") (pinfunction "D+_3") (pintype "passive"))
    )
    (net (code "26") (name "3V3") (class "Default")
      (node (ref "C9") (pin "2") (pinfunction "2_2") (pintype "passive"))
      (node (ref "U14") (pin "17") (pinfunction "3V3OUT_17") (pintype "passive"))
    )
    (net (code "27") (name "5V") (class "Default")
      (node (ref "C14") (pin "1") (pinfunction "1_1") (pintype "passive"))
      (node (ref "C15") (pin "2") (pinfunction "2_2") (pintype "passive"))
      (node (ref "D13") (pin "2") (pinfunction "K_2") (pintype "passive"))
      (node (ref "FB1") (pin "1") (pinfunction "1_1") (pintype "passive"))
      (node (ref "L1") (pin "2") (pinfunction "2_2") (pintype "passive"))
      (node (ref "R1") (pin "2") (pinfunction "2_2") (pintype "passive"))
      (node (ref "R10") (pin "2") (pinfunction "2_2") (pintype "passive"))
      (node (ref "R11") (pin "2") (pinfunction "2_2") (pintype "passive"))
      (node (ref "R12") (pin "2") (pinfunction "2_2") (pintype "passive"))
      (node (ref "R2") (pin "2") (pinfunction "2_2") (pintype "passive"))
      (node (ref "R21") (pin "2") (pinfunction "2_2") (pintype "passive"))
      (node (ref "R22") (pin "2") (pinfunction "2_2") (pintype "passive"))
      (node (ref "R23") (pin "2") (pinfunction "2_2") (pintype "passive"))
      (node (ref "R24") (pin "2") (pinfunction "2_2") (pintype "passive"))
      (node (ref "R3") (pin "2") (pinfunction "2_2") (pintype "passive"))
      (node (ref "R36") (pin "2") (pinfunction "2_2") (pintype "passive"))
      (node (ref "R4") (pin "2") (pinfunction "2_2") (pintype "passive"))
      (node (ref "R9") (pin "2") (pinfunction "2_2") (pintype "passive"))
      (node (ref "U15") (pin "4") (pinfunction "FB_4") (pintype "passive"))
    )
    (net (code "28") (name "5V_VDD") (class "Default")
      (node (ref "C10") (pin "2") (pinfunction "2_2") (pintype "passive"))
      (node (ref "C11") (pin "2") (pinfunction "2_2") (pintype "passive"))
      (node (ref "C4") (pin "2") (pinfunction "2_2") (pintype "passive"))
      (node (ref "C6") (pin "2") (pinfunction "2_2") (pintype "passive"))
      (node (ref "C7") (pin "2") (pinfunction "2_2") (pintype "passive"))
      (node (ref "C8") (pin "1") (pinfunction "1_1") (pintype "passive"))
      (node (ref "CN13") (pin "2") (pinfunction "2_2") (pintype "passive"))
      (node (ref "D14") (pin "2") (pinfunction "K_2") (pintype "passive"))
      (node (ref "LCD1") (pin "2") (pinfunction "VDD_2") (pintype "passive"))
      (node (ref "LED13") (pin "1") (pinfunction "A_1") (pintype "passive"))
      (node (ref "LED14") (pin "1") (pinfunction "A_1") (pintype "passive"))
      (node (ref "R29") (pin "2") (pinfunction "2_2") (pintype "passive"))
      (node (ref "R30") (pin "2") (pinfunction "2_2") (pintype "passive"))
      (node (ref "R35") (pin "1") (pinfunction "1_1") (pintype "passive"))
      (node (ref "U13") (pin "18") (pinfunction "AVCC_18") (pintype "passive"))
      (node (ref "U13") (pin "4") (pinfunction "VCC_4") (pintype "passive"))
      (node (ref "U13") (pin "6") (pinfunction "VCC_6") (pintype "passive"))
      (node (ref "U14") (pin "20") (pinfunction "VCC_20") (pintype "passive"))
      (node (ref "VR1") (pin "1") (pinfunction "1_1") (pintype "passive"))
    )
    (net (code "29") (name "12V") (class "Default")
      (node (ref "C12") (pin "1") (pinfunction "1_1") (pintype "passive"))
      (node (ref "C13") (pin "2") (pinfunction "2_2") (pintype "passive"))
      (node (ref "CN15") (pin "1") (pinfunction "T_1") (pintype "passive"))
      (node (ref "D1") (pin "2") (pinfunction "K_2") (pintype "passive"))
      (node (ref "D2") (pin "2") (pinfunction "K_2") (pintype "passive"))
      (node (ref "D3") (pin "2") (pinfunction "K_2") (pintype "passive"))
      (node (ref "D4") (pin "2") (pinfunction "K_2") (pintype "passive"))
      (node (ref "D5") (pin "2") (pinfunction "K_2") (pintype "passive"))
      (node (ref "D6") (pin "2") (pinfunction "K_2") (pintype "passive"))
      (node (ref "D7") (pin "2") (pinfunction "K_2") (pintype "passive"))
      (node (ref "D8") (pin "2") (pinfunction "K_2") (pintype "passive"))
      (node (ref "Q10") (pin "2") (pinfunction "D_2") (pintype "passive"))
      (node (ref "Q11") (pin "2") (pinfunction "D_2") (pintype "passive"))
      (node (ref "Q12") (pin "2") (pinfunction "D_2") (pintype "passive"))
      (node (ref "Q9") (pin "2") (pinfunction "D_2") (pintype "passive"))
      (node (ref "R17") (pin "2") (pinfunction "2_2") (pintype "passive"))
      (node (ref "R18") (pin "2") (pinfunction "2_2") (pintype "passive"))
      (node (ref "R19") (pin "2") (pinfunction "2_2") (pintype "passive"))
      (node (ref "R20") (pin "2") (pinfunction "2_2") (pintype "passive"))
      (node (ref "RL1") (pin "1") (pinfunction "1_1") (pintype "passive"))
      (node (ref "RL2") (pin "1") (pinfunction "1_1") (pintype "passive"))
      (node (ref "RL3") (pin "1") (pinfunction "1_1") (pintype "passive"))
      (node (ref "RL4") (pin "1") (pinfunction "1_1") (pintype "passive"))
      (node (ref "RL5") (pin "1") (pinfunction "1_1") (pintype "passive"))
      (node (ref "RL6") (pin "1") (pinfunction "1_1") (pintype "passive"))
      (node (ref "RL7") (pin "1") (pinfunction "1_1") (pintype "passive"))
      (node (ref "RL8") (pin "1") (pinfunction "1_1") (pintype "passive"))
      (node (ref "U1") (pin "4") (pinfunction "C_4") (pintype "passive"))
      (node (ref "U15") (pin "1") (pinfunction "IN_1") (pintype "passive"))
      (node (ref "U2") (pin "4") (pinfunction "C_4") (pintype "passive"))
      (node (ref "U3") (pin "4") (pinfunction "C_4") (pintype "passive"))
      (node (ref "U4") (pin "4") (pinfunction "C_4") (pintype "passive"))
      (node (ref "U5") (pin "4") (pinfunction "C_4") (pintype "passive"))
      (node (ref "U6") (pin "4") (pinfunction "C_4") (pintype "passive"))
      (node (ref "U7") (pin "4") (pinfunction "C_4") (pintype "passive"))
      (node (ref "U8") (pin "4") (pinfunction "C_4") (pintype "passive"))
    )
    (net (code "30") (name "DGND") (class "Default")
      (node (ref "C1") (pin "2") (pinfunction "2_2") (pintype "passive"))
      (node (ref "C10") (pin "1") (pinfunction "1_1") (pintype "passive"))
      (node (ref "C11") (pin "1") (pinfunction "1_1") (pintype "passive"))
      (node (ref "C16") (pin "1") (pinfunction "1_1") (pintype "passive"))
      (node (ref "C17") (pin "1") (pinfunction "1_1") (pintype "passive"))
      (node (ref "C2") (pin "2") (pinfunction "2_2") (pintype "passive"))
      (node (ref "C3") (pin "2") (pinfunction "2_2") (pintype "passive"))
      (node (ref "C4") (pin "1") (pinfunction "1_1") (pintype "passive"))
      (node (ref "C6") (pin "1") (pinfunction "1_1") (pintype "passive"))
      (node (ref "C7") (pin "1") (pinfunction "1_1") (pintype "passive"))
      (node (ref "C8") (pin "2") (pinfunction "2_2") (pintype "passive"))
      (node (ref "C9") (pin "1") (pinfunction "1_1") (pintype "passive"))
      (node (ref "CN13") (pin "6") (pinfunction "6_6") (pintype "passive"))
      (node (ref "CN14") (pin "2") (pinfunction "2_2") (pintype "passive"))
      (node (ref "CN14") (pin "4") (pinfunction "4_4") (pintype "passive"))
      (node (ref "LCD1") (pin "1") (pinfunction "VSS_1") (pintype "passive"))
      (node (ref "LCD1") (pin "16") (pinfunction "K_16") (pintype "passive"))
      (node (ref "LCD1") (pin "5") (pinfunction "R/W_5") (pintype "passive"))
      (node (ref "R37") (pin "1") (pinfunction "1_1") (pintype "passive"))
      (node (ref "SW1") (pin "1") (pintype "passive"))
      (node (ref "U13") (pin "21") (pinfunction "AGND_21") (pintype "passive"))
      (node (ref "U13") (pin "3") (pinfunction "GND_3") (pintype "passive"))
      (node (ref "U13") (pin "5") (pinfunction "GND_5") (pintype "passive"))
      (node (ref "U14") (pin "18") (pinfunction "GND_18") (pintype "passive"))
      (node (ref "U14") (pin "21") (pinfunction "GND_21") (pintype "passive"))
      (node (ref "U14") (pin "25") (pinfunction "AGND_25") (pintype "passive"))
      (node (ref "U14") (pin "26") (pinfunction "TEST_26") (pintype "passive"))
      (node (ref "U14") (pin "7") (pinfunction "GND_7") (pintype "passive"))
      (node (ref "USB1") (pin "1") (pinfunction "GND_1") (pintype "power_in"))
      (node (ref "VR1") (pin "3") (pinfunction "3_3") (pintype "passive"))
    )
    (net (code "31") (name "GND") (class "Default")
      (node (ref "C12") (pin "2") (pinfunction "2_2") (pintype "passive"))
      (node (ref "C13") (pin "1") (pinfunction "1_1") (pintype "passive"))
      (node (ref "C14") (pin "2") (pinfunction "2_2") (pintype "passive"))
      (node (ref "C15") (pin "1") (pinfunction "1_1") (pintype "passive"))
      (node (ref "CN10") (pin "2") (pinfunction "2_2") (pintype "passive"))
      (node (ref "CN11") (pin "2") (pinfunction "2_2") (pintype "passive"))
      (node (ref "CN12") (pin "2") (pinfunction "2_2") (pintype "passive"))
      (node (ref "CN15") (pin "2") (pinfunction "TN_2") (pintype "passive"))
      (node (ref "CN15") (pin "3") (pinfunction "S_3") (pintype "power_in"))
      (node (ref "CN9") (pin "2") (pinfunction "2_2") (pintype "passive"))
      (node (ref "D10") (pin "1") (pinfunction "A_1") (pintype "passive"))
      (node (ref "D11") (pin "1") (pinfunction "A_1") (pintype "passive"))
      (node (ref "D12") (pin "1") (pinfunction "A_1") (pintype "passive"))
      (node (ref "D13") (pin "1") (pinfunction "A_1") (pintype "passive"))
      (node (ref "D9") (pin "1") (pinfunction "A_1") (pintype "passive"))
      (node (ref "LED15") (pin "2") (pinfunction "K_2") (pintype "passive"))
      (node (ref "Q1") (pin "2") (pinfunction "E_2") (pintype "passive"))
      (node (ref "Q2") (pin "2") (pinfunction "E_2") (pintype "passive"))
      (node (ref "Q3") (pin "2") (pinfunction "E_2") (pintype "passive"))
      (node (ref "Q4") (pin "2") (pinfunction "E_2") (pintype "passive"))
      (node (ref "Q5") (pin "2") (pinfunction "E_2") (pintype "passive"))
      (node (ref "Q6") (pin "2") (pinfunction "E_2") (pintype "passive"))
      (node (ref "Q7") (pin "2") (pinfunction "E_2") (pintype "passive"))
      (node (ref "Q8") (pin "2") (pinfunction "E_2") (pintype "passive"))
      (node (ref "R37") (pin "2") (pinfunction "2_2") (pintype "passive"))
      (node (ref "U10") (pin "3") (pinfunction "E_3") (pintype "passive"))
      (node (ref "U11") (pin "3") (pinfunction "E_3") (pintype "passive"))
      (node (ref "U12") (pin "3") (pinfunction "E_3") (pintype "passive"))
      (node (ref "U15") (pin "3") (pinfunction "GND_3") (pintype "passive"))
      (node (ref "U15") (pin "5") (pinfunction "EN_5") (pintype "passive"))
      (node (ref "U9") (pin "3") (pinfunction "E_3") (pintype "passive"))
    )
    (net (code "32") (name "Net-(CN1-Pad1)") (class "Default")
      (node (ref "CN1") (pin "1") (pinfunction "1_1") (pintype "passive"))
      (node (ref "RL1") (pin "3") (pinfunction "3_3") (pintype "passive"))
    )
    (net (code "33") (name "Net-(CN1-Pad2)") (class "Default")
      (node (ref "CN1") (pin "2") (pinfunction "2_2") (pintype "passive"))
      (node (ref "RL1") (pin "4") (pinfunction "4_4") (pintype "passive"))
    )
    (net (code "34") (name "Net-(CN2-Pad1)") (class "Default")
      (node (ref "CN2") (pin "1") (pinfunction "1_1") (pintype "passive"))
      (node (ref "RL2") (pin "3") (pinfunction "3_3") (pintype "passive"))
    )
    (net (code "35") (name "Net-(CN2-Pad2)") (class "Default")
      (node (ref "CN2") (pin "2") (pinfunction "2_2") (pintype "passive"))
      (node (ref "RL2") (pin "4") (pinfunction "4_4") (pintype "passive"))
    )
    (net (code "36") (name "Net-(CN3-Pad1)") (class "Default")
      (node (ref "CN3") (pin "1") (pinfunction "1_1") (pintype "passive"))
      (node (ref "RL3") (pin "3") (pinfunction "3_3") (pintype "passive"))
    )
    (net (code "37") (name "Net-(CN3-Pad2)") (class "Default")
      (node (ref "CN3") (pin "2") (pinfunction "2_2") (pintype "passive"))
      (node (ref "RL3") (pin "4") (pinfunction "4_4") (pintype "passive"))
    )
    (net (code "38") (name "Net-(CN4-Pad1)") (class "Default")
      (node (ref "CN4") (pin "1") (pinfunction "1_1") (pintype "passive"))
      (node (ref "RL4") (pin "3") (pinfunction "3_3") (pintype "passive"))
    )
    (net (code "39") (name "Net-(CN4-Pad2)") (class "Default")
      (node (ref "CN4") (pin "2") (pinfunction "2_2") (pintype "passive"))
      (node (ref "RL4") (pin "4") (pinfunction "4_4") (pintype "passive"))
    )
    (net (code "40") (name "Net-(CN5-Pad1)") (class "Default")
      (node (ref "CN5") (pin "1") (pinfunction "1_1") (pintype "passive"))
      (node (ref "RL5") (pin "3") (pinfunction "3_3") (pintype "passive"))
    )
    (net (code "41") (name "Net-(CN5-Pad2)") (class "Default")
      (node (ref "CN5") (pin "2") (pinfunction "2_2") (pintype "passive"))
      (node (ref "RL5") (pin "4") (pinfunction "4_4") (pintype "passive"))
    )
    (net (code "42") (name "Net-(CN6-Pad1)") (class "Default")
      (node (ref "CN6") (pin "1") (pinfunction "1_1") (pintype "passive"))
      (node (ref "RL6") (pin "3") (pinfunction "3_3") (pintype "passive"))
    )
    (net (code "43") (name "Net-(CN6-Pad2)") (class "Default")
      (node (ref "CN6") (pin "2") (pinfunction "2_2") (pintype "passive"))
      (node (ref "RL6") (pin "4") (pinfunction "4_4") (pintype "passive"))
    )
    (net (code "44") (name "Net-(CN7-Pad1)") (class "Default")
      (node (ref "CN7") (pin "1") (pinfunction "1_1") (pintype "passive"))
      (node (ref "RL7") (pin "3") (pinfunction "3_3") (pintype "passive"))
    )
    (net (code "45") (name "Net-(CN7-Pad2)") (class "Default")
      (node (ref "CN7") (pin "2") (pinfunction "2_2") (pintype "passive"))
      (node (ref "RL7") (pin "4") (pinfunction "4_4") (pintype "passive"))
    )
    (net (code "46") (name "Net-(CN8-Pad1)") (class "Default")
      (node (ref "CN8") (pin "1") (pinfunction "1_1") (pintype "passive"))
      (node (ref "RL8") (pin "3") (pinfunction "3_3") (pintype "passive"))
    )
    (net (code "47") (name "Net-(CN8-Pad2)") (class "Default")
      (node (ref "CN8") (pin "2") (pinfunction "2_2") (pintype "passive"))
      (node (ref "RL8") (pin "4") (pinfunction "4_4") (pintype "passive"))
    )
    (net (code "48") (name "Net-(D1-A)") (class "Default")
      (node (ref "D1") (pin "1") (pinfunction "A_1") (pintype "passive"))
      (node (ref "Q1") (pin "3") (pinfunction "C_3") (pintype "passive"))
      (node (ref "RL1") (pin "2") (pinfunction "2_2") (pintype "passive"))
    )
    (net (code "49") (name "Net-(D2-A)") (class "Default")
      (node (ref "D2") (pin "1") (pinfunction "A_1") (pintype "passive"))
      (node (ref "Q2") (pin "3") (pinfunction "C_3") (pintype "passive"))
      (node (ref "RL2") (pin "2") (pinfunction "2_2") (pintype "passive"))
    )
    (net (code "50") (name "Net-(D3-A)") (class "Default")
      (node (ref "D3") (pin "1") (pinfunction "A_1") (pintype "passive"))
      (node (ref "Q3") (pin "3") (pinfunction "C_3") (pintype "passive"))
      (node (ref "RL3") (pin "2") (pinfunction "2_2") (pintype "passive"))
    )
    (net (code "51") (name "Net-(D4-A)") (class "Default")
      (node (ref "D4") (pin "1") (pinfunction "A_1") (pintype "passive"))
      (node (ref "Q4") (pin "3") (pinfunction "C_3") (pintype "passive"))
      (node (ref "RL4") (pin "2") (pinfunction "2_2") (pintype "passive"))
    )
    (net (code "52") (name "Net-(D5-A)") (class "Default")
      (node (ref "D5") (pin "1") (pinfunction "A_1") (pintype "passive"))
      (node (ref "Q5") (pin "3") (pinfunction "C_3") (pintype "passive"))
      (node (ref "RL5") (pin "2") (pinfunction "2_2") (pintype "passive"))
    )
    (net (code "53") (name "Net-(D6-A)") (class "Default")
      (node (ref "D6") (pin "1") (pinfunction "A_1") (pintype "passive"))
      (node (ref "Q6") (pin "3") (pinfunction "C_3") (pintype "passive"))
      (node (ref "RL6") (pin "2") (pinfunction "2_2") (pintype "passive"))
    )
    (net (code "54") (name "Net-(D7-A)") (class "Default")
      (node (ref "D7") (pin "1") (pinfunction "A_1") (pintype "passive"))
      (node (ref "Q7") (pin "3") (pinfunction "C_3") (pintype "passive"))
      (node (ref "RL7") (pin "2") (pinfunction "2_2") (pintype "passive"))
    )
    (net (code "55") (name "Net-(D8-A)") (class "Default")
      (node (ref "D8") (pin "1") (pinfunction "A_1") (pintype "passive"))
      (node (ref "Q8") (pin "3") (pinfunction "C_3") (pintype "passive"))
      (node (ref "RL8") (pin "2") (pinfunction "2_2") (pintype "passive"))
    )
    (net (code "56") (name "Net-(D9-K)") (class "Default")
      (node (ref "CN9") (pin "1") (pinfunction "1_1") (pintype "passive"))
      (node (ref "D9") (pin "2") (pinfunction "K_2") (pintype "passive"))
      (node (ref "Q9") (pin "3") (pinfunction "S_3") (pintype "passive"))
    )
    (net (code "57") (name "Net-(D10-K)") (class "Default")
      (node (ref "CN10") (pin "1") (pinfunction "1_1") (pintype "passive"))
      (node (ref "D10") (pin "2") (pinfunction "K_2") (pintype "passive"))
      (node (ref "Q10") (pin "3") (pinfunction "S_3") (pintype "passive"))
    )
    (net (code "58") (name "Net-(D11-K)") (class "Default")
      (node (ref "CN11") (pin "1") (pinfunction "1_1") (pintype "passive"))
      (node (ref "D11") (pin "2") (pinfunction "K_2") (pintype "passive"))
      (node (ref "Q11") (pin "3") (pinfunction "S_3") (pintype "passive"))
    )
    (net (code "59") (name "Net-(D12-K)") (class "Default")
      (node (ref "CN12") (pin "1") (pinfunction "1_1") (pintype "passive"))
      (node (ref "D12") (pin "2") (pinfunction "K_2") (pintype "passive"))
      (node (ref "Q12") (pin "3") (pinfunction "S_3") (pintype "passive"))
    )
    (net (code "60") (name "Net-(FB1-Pad2)") (class "Default")
      (node (ref "FB1") (pin "2") (pinfunction "2_2") (pintype "passive"))
      (node (ref "R35") (pin "2") (pinfunction "2_2") (pintype "passive"))
    )
    (net (code "61") (name "Net-(LCD1-A)") (class "Default")
      (node (ref "LCD1") (pin "15") (pinfunction "A_15") (pintype "passive"))
      (node (ref "R30") (pin "1") (pinfunction "1_1") (pintype "passive"))
    )
    (net (code "62") (name "Net-(LCD1-VEE)") (class "Default")
      (node (ref "LCD1") (pin "3") (pinfunction "VEE_3") (pintype "passive"))
      (node (ref "VR1") (pin "2") (pinfunction "2_2") (pintype "passive"))
    )
    (net (code "63") (name "Net-(LED1-A)") (class "Default")
      (node (ref "LED1") (pin "1") (pinfunction "A_1") (pintype "passive"))
      (node (ref "U1") (pin "2") (pinfunction "K_2") (pintype "passive"))
    )
    (net (code "64") (name "Net-(LED2-A)") (class "Default")
      (node (ref "LED2") (pin "1") (pinfunction "A_1") (pintype "passive"))
      (node (ref "U2") (pin "2") (pinfunction "K_2") (pintype "passive"))
    )
    (net (code "65") (name "Net-(LED3-A)") (class "Default")
      (node (ref "LED3") (pin "1") (pinfunction "A_1") (pintype "passive"))
      (node (ref "U3") (pin "2") (pinfunction "K_2") (pintype "passive"))
    )
    (net (code "66") (name "Net-(LED4-A)") (class "Default")
      (node (ref "LED4") (pin "1") (pinfunction "A_1") (pintype "passive"))
      (node (ref "U4") (pin "2") (pinfunction "K_2") (pintype "passive"))
    )
    (net (code "67") (name "Net-(LED5-A)") (class "Default")
      (node (ref "LED5") (pin "1") (pinfunction "A_1") (pintype "passive"))
      (node (ref "U5") (pin "2") (pinfunction "K_2") (pintype "passive"))
    )
    (net (code "68") (name "Net-(LED6-A)") (class "Default")
      (node (ref "LED6") (pin "1") (pinfunction "A_1") (pintype "passive"))
      (node (ref "U6") (pin "2") (pinfunction "K_2") (pintype "passive"))
    )
    (net (code "69") (name "Net-(LED7-A)") (class "Default")
      (node (ref "LED7") (pin "1") (pinfunction "A_1") (pintype "passive"))
      (node (ref "U7") (pin "2") (pinfunction "K_2") (pintype "passive"))
    )
    (net (code "70") (name "Net-(LED8-A)") (class "Default")
      (node (ref "LED8") (pin "1") (pinfunction "A_1") (pintype "passive"))
      (node (ref "U8") (pin "2") (pinfunction "K_2") (pintype "passive"))
    )
    (net (code "71") (name "Net-(LED9-A)") (class "Default")
      (node (ref "LED9") (pin "1") (pinfunction "A_1") (pintype "passive"))
      (node (ref "U9") (pin "2") (pinfunction "K_2") (pintype "passive"))
    )
    (net (code "72") (name "Net-(LED10-A)") (class "Default")
      (node (ref "LED10") (pin "1") (pinfunction "A_1") (pintype "passive"))
      (node (ref "U10") (pin "2") (pinfunction "K_2") (pintype "passive"))
    )
    (net (code "73") (name "Net-(LED11-A)") (class "Default")
      (node (ref "LED11") (pin "1") (pinfunction "A_1") (pintype "passive"))
      (node (ref "U11") (pin "2") (pinfunction "K_2") (pintype "passive"))
    )
    (net (code "74") (name "Net-(LED12-A)") (class "Default")
      (node (ref "LED12") (pin "1") (pinfunction "A_1") (pintype "passive"))
      (node (ref "U12") (pin "2") (pinfunction "K_2") (pintype "passive"))
    )
    (net (code "75") (name "Net-(LED13-K)") (class "Default")
      (node (ref "LED13") (pin "2") (pinfunction "K_2") (pintype "passive"))
      (node (ref "R31") (pin "1") (pinfunction "1_1") (pintype "passive"))
    )
    (net (code "76") (name "Net-(LED14-K)") (class "Default")
      (node (ref "LED14") (pin "2") (pinfunction "K_2") (pintype "passive"))
      (node (ref "R32") (pin "1") (pinfunction "1_1") (pintype "passive"))
    )
    (net (code "77") (name "Net-(LED15-A)") (class "Default")
      (node (ref "LED15") (pin "1") (pinfunction "A_1") (pintype "passive"))
      (node (ref "R36") (pin "1") (pinfunction "1_1") (pintype "passive"))
    )
    (net (code "78") (name "Net-(Q1-B)") (class "Default")
      (node (ref "Q1") (pin "1") (pinfunction "B_1") (pintype "passive"))
      (node (ref "R5") (pin "1") (pinfunction "1_1") (pintype "passive"))
    )
    (net (code "79") (name "Net-(Q2-B)") (class "Default")
      (node (ref "Q2") (pin "1") (pinfunction "B_1") (pintype "passive"))
      (node (ref "R6") (pin "1") (pinfunction "1_1") (pintype "passive"))
    )
    (net (code "80") (name "Net-(Q3-B)") (class "Default")
      (node (ref "Q3") (pin "1") (pinfunction "B_1") (pintype "passive"))
      (node (ref "R7") (pin "1") (pinfunction "1_1") (pintype "passive"))
    )
    (net (code "81") (name "Net-(Q4-B)") (class "Default")
      (node (ref "Q4") (pin "1") (pinfunction "B_1") (pintype "passive"))
      (node (ref "R8") (pin "1") (pinfunction "1_1") (pintype "passive"))
    )
    (net (code "82") (name "Net-(Q5-B)") (class "Default")
      (node (ref "Q5") (pin "1") (pinfunction "B_1") (pintype "passive"))
      (node (ref "R13") (pin "1") (pinfunction "1_1") (pintype "passive"))
    )
    (net (code "83") (name "Net-(Q6-B)") (class "Default")
      (node (ref "Q6") (pin "1") (pinfunction "B_1") (pintype "passive"))
      (node (ref "R14") (pin "1") (pinfunction "1_1") (pintype "passive"))
    )
    (net (code "84") (name "Net-(Q7-B)") (class "Default")
      (node (ref "Q7") (pin "1") (pinfunction "B_1") (pintype "passive"))
      (node (ref "R15") (pin "1") (pinfunction "1_1") (pintype "passive"))
    )
    (net (code "85") (name "Net-(Q8-B)") (class "Default")
      (node (ref "Q8") (pin "1") (pinfunction "B_1") (pintype "passive"))
      (node (ref "R16") (pin "1") (pinfunction "1_1") (pintype "passive"))
    )
    (net (code "86") (name "Net-(Q9-G)") (class "Default")
      (node (ref "Q9") (pin "1") (pinfunction "G_1") (pintype "passive"))
      (node (ref "R17") (pin "1") (pinfunction "1_1") (pintype "passive"))
      (node (ref "R25") (pin "1") (pinfunction "1_1") (pintype "passive"))
    )
    (net (code "87") (name "Net-(Q10-G)") (class "Default")
      (node (ref "Q10") (pin "1") (pinfunction "G_1") (pintype "passive"))
      (node (ref "R18") (pin "1") (pinfunction "1_1") (pintype "passive"))
      (node (ref "R26") (pin "1") (pinfunction "1_1") (pintype "passive"))
    )
    (net (code "88") (name "Net-(Q11-G)") (class "Default")
      (node (ref "Q11") (pin "1") (pinfunction "G_1") (pintype "passive"))
      (node (ref "R19") (pin "1") (pinfunction "1_1") (pintype "passive"))
      (node (ref "R27") (pin "1") (pinfunction "1_1") (pintype "passive"))
    )
    (net (code "89") (name "Net-(Q12-G)") (class "Default")
      (node (ref "Q12") (pin "1") (pinfunction "G_1") (pintype "passive"))
      (node (ref "R20") (pin "1") (pinfunction "1_1") (pintype "passive"))
      (node (ref "R28") (pin "1") (pinfunction "1_1") (pintype "passive"))
    )
    (net (code "90") (name "Net-(U1-A)") (class "Default")
      (node (ref "R1") (pin "1") (pinfunction "1_1") (pintype "passive"))
      (node (ref "U1") (pin "1") (pinfunction "A_1") (pintype "passive"))
    )
    (net (code "91") (name "Net-(U1-E)") (class "Default")
      (node (ref "R5") (pin "2") (pinfunction "2_2") (pintype "passive"))
      (node (ref "U1") (pin "3") (pinfunction "E_3") (pintype "passive"))
    )
    (net (code "92") (name "Net-(U2-A)") (class "Default")
      (node (ref "R2") (pin "1") (pinfunction "1_1") (pintype "passive"))
      (node (ref "U2") (pin "1") (pinfunction "A_1") (pintype "passive"))
    )
    (net (code "93") (name "Net-(U2-E)") (class "Default")
      (node (ref "R6") (pin "2") (pinfunction "2_2") (pintype "passive"))
      (node (ref "U2") (pin "3") (pinfunction "E_3") (pintype "passive"))
    )
    (net (code "94") (name "Net-(U3-A)") (class "Default")
      (node (ref "R3") (pin "1") (pinfunction "1_1") (pintype "passive"))
      (node (ref "U3") (pin "1") (pinfunction "A_1") (pintype "passive"))
    )
    (net (code "95") (name "Net-(U3-E)") (class "Default")
      (node (ref "R7") (pin "2") (pinfunction "2_2") (pintype "passive"))
      (node (ref "U3") (pin "3") (pinfunction "E_3") (pintype "passive"))
    )
    (net (code "96") (name "Net-(U4-A)") (class "Default")
      (node (ref "R4") (pin "1") (pinfunction "1_1") (pintype "passive"))
      (node (ref "U4") (pin "1") (pinfunction "A_1") (pintype "passive"))
    )
    (net (code "97") (name "Net-(U4-E)") (class "Default")
      (node (ref "R8") (pin "2") (pinfunction "2_2") (pintype "passive"))
      (node (ref "U4") (pin "3") (pinfunction "E_3") (pintype "passive"))
    )
    (net (code "98") (name "Net-(U5-A)") (class "Default")
      (node (ref "R9") (pin "1") (pinfunction "1_1") (pintype "passive"))
      (node (ref "U5") (pin "1") (pinfunction "A_1") (pintype "passive"))
    )
    (net (code "99") (name "Net-(U5-E)") (class "Default")
      (node (ref "R13") (pin "2") (pinfunction "2_2") (pintype "passive"))
      (node (ref "U5") (pin "3") (pinfunction "E_3") (pintype "passive"))
    )
    (net (code "100") (name "Net-(U6-A)") (class "Default")
      (node (ref "R10") (pin "1") (pinfunction "1_1") (pintype "passive"))
      (node (ref "U6") (pin "1") (pinfunction "A_1") (pintype "passive"))
    )
    (net (code "101") (name "Net-(U6-E)") (class "Default")
      (node (ref "R14") (pin "2") (pinfunction "2_2") (pintype "passive"))
      (node (ref "U6") (pin "3") (pinfunction "E_3") (pintype "passive"))
    )
    (net (code "102") (name "Net-(U7-A)") (class "Default")
      (node (ref "R11") (pin "1") (pinfunction "1_1") (pintype "passive"))
      (node (ref "U7") (pin "1") (pinfunction "A_1") (pintype "passive"))
    )
    (net (code "103") (name "Net-(U7-E)") (class "Default")
      (node (ref "R15") (pin "2") (pinfunction "2_2") (pintype "passive"))
      (node (ref "U7") (pin "3") (pinfunction "E_3") (pintype "passive"))
    )
    (net (code "104") (name "Net-(U8-A)") (class "Default")
      (node (ref "R12") (pin "1") (pinfunction "1_1") (pintype "passive"))
      (node (ref "U8") (pin "1") (pinfunction "A_1") (pintype "passive"))
    )
    (net (code "105") (name "Net-(U8-E)") (class "Default")
      (node (ref "R16") (pin "2") (pinfunction "2_2") (pintype "passive"))
      (node (ref "U8") (pin "3") (pinfunction "E_3") (pintype "passive"))
    )
    (net (code "106") (name "Net-(U9-A)") (class "Default")
      (node (ref "R21") (pin "1") (pinfunction "1_1") (pintype "passive"))
      (node (ref "U9") (pin "1") (pinfunction "A_1") (pintype "passive"))
    )
    (net (code "107") (name "Net-(U9-C)") (class "Default")
      (node (ref "R25") (pin "2") (pinfunction "2_2") (pintype "passive"))
      (node (ref "U9") (pin "4") (pinfunction "C_4") (pintype "passive"))
    )
    (net (code "108") (name "Net-(U10-A)") (class "Default")
      (node (ref "R22") (pin "1") (pinfunction "1_1") (pintype "passive"))
      (node (ref "U10") (pin "1") (pinfunction "A_1") (pintype "passive"))
    )
    (net (code "109") (name "Net-(U10-C)") (class "Default")
      (node (ref "R26") (pin "2") (pinfunction "2_2") (pintype "passive"))
      (node (ref "U10") (pin "4") (pinfunction "C_4") (pintype "passive"))
    )
    (net (code "110") (name "Net-(U11-A)") (class "Default")
      (node (ref "R23") (pin "1") (pinfunction "1_1") (pintype "passive"))
      (node (ref "U11") (pin "1") (pinfunction "A_1") (pintype "passive"))
    )
    (net (code "111") (name "Net-(U11-C)") (class "Default")
      (node (ref "R27") (pin "2") (pinfunction "2_2") (pintype "passive"))
      (node (ref "U11") (pin "4") (pinfunction "C_4") (pintype "passive"))
    )
    (net (code "112") (name "Net-(U12-A)") (class "Default")
      (node (ref "R24") (pin "1") (pinfunction "1_1") (pintype "passive"))
      (node (ref "U12") (pin "1") (pinfunction "A_1") (pintype "passive"))
    )
    (net (code "113") (name "Net-(U12-C)") (class "Default")
      (node (ref "R28") (pin "2") (pinfunction "2_2") (pintype "passive"))
      (node (ref "U12") (pin "4") (pinfunction "C_4") (pintype "passive"))
    )
    (net (code "114") (name "Net-(U13-AREF)") (class "Default")
      (node (ref "C3") (pin "1") (pinfunction "1_1") (pintype "passive"))
      (node (ref "U13") (pin "20") (pinfunction "AREF_20") (pintype "passive"))
    )
    (net (code "115") (name "Net-(U13-PB6{slash}PCINT6{slash}XTAL1{slash}TOSC1)") (class "Default")
      (node (ref "C2") (pin "1") (pinfunction "1_1") (pintype "passive"))
      (node (ref "U13") (pin "7") (pinfunction "PB6/PCINT6/XTAL1/TOSC1_7") (pintype "passive"))
      (node (ref "XT1") (pin "1") (pinfunction "1_1") (pintype "passive"))
    )
    (net (code "116") (name "Net-(U13-PB7{slash}PCINT7{slash}XTAL2{slash}TOSC2)") (class "Default")
      (node (ref "C1") (pin "1") (pinfunction "1_1") (pintype "passive"))
      (node (ref "U13") (pin "8") (pinfunction "PB7/PCINT7/XTAL2/TOSC2_8") (pintype "passive"))
      (node (ref "XT1") (pin "2") (pinfunction "2_2") (pintype "passive"))
    )
    (net (code "117") (name "Net-(U13-PD0{slash}PCINT16{slash}RXD)") (class "Default")
      (node (ref "R34") (pin "2") (pinfunction "2_2") (pintype "passive"))
      (node (ref "U13") (pin "30") (pinfunction "PD0/PCINT16/RXD_30") (pintype "passive"))
    )
    (net (code "118") (name "Net-(U13-PD1{slash}PCINT17{slash}TXD)") (class "Default")
      (node (ref "R33") (pin "2") (pinfunction "2_2") (pintype "passive"))
      (node (ref "U13") (pin "31") (pinfunction "PD1/PCINT17/TXD_31") (pintype "passive"))
    )
    (net (code "119") (name "Net-(U14-CBUS0)") (class "Default")
      (node (ref "R31") (pin "2") (pinfunction "2_2") (pintype "passive"))
      (node (ref "U14") (pin "23") (pinfunction "CBUS0_23") (pintype "passive"))
    )
    (net (code "120") (name "Net-(U14-CBUS1)") (class "Default")
      (node (ref "R32") (pin "2") (pinfunction "2_2") (pintype "passive"))
      (node (ref "U14") (pin "22") (pinfunction "CBUS1_22") (pintype "passive"))
    )
    (net (code "121") (name "Net-(U14-DTR#)") (class "Default")
      (node (ref "C5") (pin "1") (pinfunction "1_1") (pintype "passive"))
      (node (ref "U14") (pin "2") (pinfunction "DTR#_2") (pintype "passive"))
    )
    (net (code "122") (name "Net-(U15-OUT)") (class "Default")
      (node (ref "L1") (pin "1") (pinfunction "1_1") (pintype "passive"))
      (node (ref "U15") (pin "2") (pinfunction "OUT_2") (pintype "passive"))
    )
    (net (code "123") (name "Net-(USB1-VBUS)") (class "Default")
      (node (ref "FUSE1") (pin "2") (pinfunction "2_2") (pintype "passive"))
      (node (ref "USB1") (pin "5") (pinfunction "VBUS_5") (pintype "power_in"))
    )
    (net (code "124") (name "USB") (class "Default")
      (node (ref "C16") (pin "2") (pinfunction "2_2") (pintype "passive"))
      (node (ref "C17") (pin "2") (pinfunction "2_2") (pintype "passive"))
      (node (ref "D14") (pin "1") (pinfunction "A_1") (pintype "passive"))
      (node (ref "FUSE1") (pin "1") (pinfunction "1_1") (pintype "passive"))
    )
    (net (code "125") (name "unconnected-(LCD1-D0-Pad7)") (class "Default")
      (node (ref "LCD1") (pin "7") (pinfunction "D0_7") (pintype "passive+no_connect"))
    )
    (net (code "126") (name "unconnected-(LCD1-D1-Pad8)") (class "Default")
      (node (ref "LCD1") (pin "8") (pinfunction "D1_8") (pintype "passive+no_connect"))
    )
    (net (code "127") (name "unconnected-(LCD1-D2-Pad9)") (class "Default")
      (node (ref "LCD1") (pin "9") (pinfunction "D2_9") (pintype "passive+no_connect"))
    )
    (net (code "128") (name "unconnected-(LCD1-D3-Pad10)") (class "Default")
      (node (ref "LCD1") (pin "10") (pinfunction "D3_10") (pintype "passive+no_connect"))
    )
    (net (code "129") (name "unconnected-(U14-CBUS2-Pad13)") (class "Default")
      (node (ref "U14") (pin "13") (pinfunction "CBUS2_13") (pintype "passive+no_connect"))
    )
    (net (code "130") (name "unconnected-(U14-CBUS3-Pad14)") (class "Default")
      (node (ref "U14") (pin "14") (pinfunction "CBUS3_14") (pintype "passive+no_connect"))
    )
    (net (code "131") (name "unconnected-(U14-CBUS4-Pad12)") (class "Default")
      (node (ref "U14") (pin "12") (pinfunction "CBUS4_12") (pintype "passive+no_connect"))
    )
    (net (code "132") (name "unconnected-(U14-CTS#-Pad11)") (class "Default")
      (node (ref "U14") (pin "11") (pinfunction "CTS#_11") (pintype "passive+no_connect"))
    )
    (net (code "133") (name "unconnected-(U14-DCD#-Pad10)") (class "Default")
      (node (ref "U14") (pin "10") (pinfunction "DCD#_10") (pintype "passive+no_connect"))
    )
    (net (code "134") (name "unconnected-(U14-DSR#-Pad9)") (class "Default")
      (node (ref "U14") (pin "9") (pinfunction "DSR#_9") (pintype "passive+no_connect"))
    )
    (net (code "135") (name "unconnected-(U14-NC1-Pad8)") (class "Default")
      (node (ref "U14") (pin "8") (pinfunction "NC1_8") (pintype "passive+no_connect"))
    )
    (net (code "136") (name "unconnected-(U14-NC2-Pad24)") (class "Default")
      (node (ref "U14") (pin "24") (pinfunction "NC2_24") (pintype "passive+no_connect"))
    )
    (net (code "137") (name "unconnected-(U14-OSCI-Pad27)") (class "Default")
      (node (ref "U14") (pin "27") (pinfunction "OSCI_27") (pintype "passive+no_connect"))
    )
    (net (code "138") (name "unconnected-(U14-OSCO-Pad28)") (class "Default")
      (node (ref "U14") (pin "28") (pinfunction "OSCO_28") (pintype "passive+no_connect"))
    )
    (net (code "139") (name "unconnected-(U14-RESET#-Pad19)") (class "Default")
      (node (ref "U14") (pin "19") (pinfunction "RESET#_19") (pintype "passive+no_connect"))
    )
    (net (code "140") (name "unconnected-(U14-RI#-Pad6)") (class "Default")
      (node (ref "U14") (pin "6") (pinfunction "RI#_6") (pintype "passive+no_connect"))
    )
    (net (code "141") (name "unconnected-(U14-RTS#-Pad3)") (class "Default")
      (node (ref "U14") (pin "3") (pinfunction "RTS#_3") (pintype "passive+no_connect"))
    )
    (net (code "142") (name "unconnected-(U14-VCCIO-Pad4)") (class "Default")
      (node (ref "U14") (pin "4") (pinfunction "VCCIO_4") (pintype "passive+no_connect"))
    )
    (net (code "143") (name "unconnected-(USB1-ID-Pad2)") (class "Default")
      (node (ref "USB1") (pin "2") (pinfunction "ID_2") (pintype "power_in+no_connect"))
    )
  )
)
